# Module_control.net
KiCad netlist of a schematic drawn in EAGLE
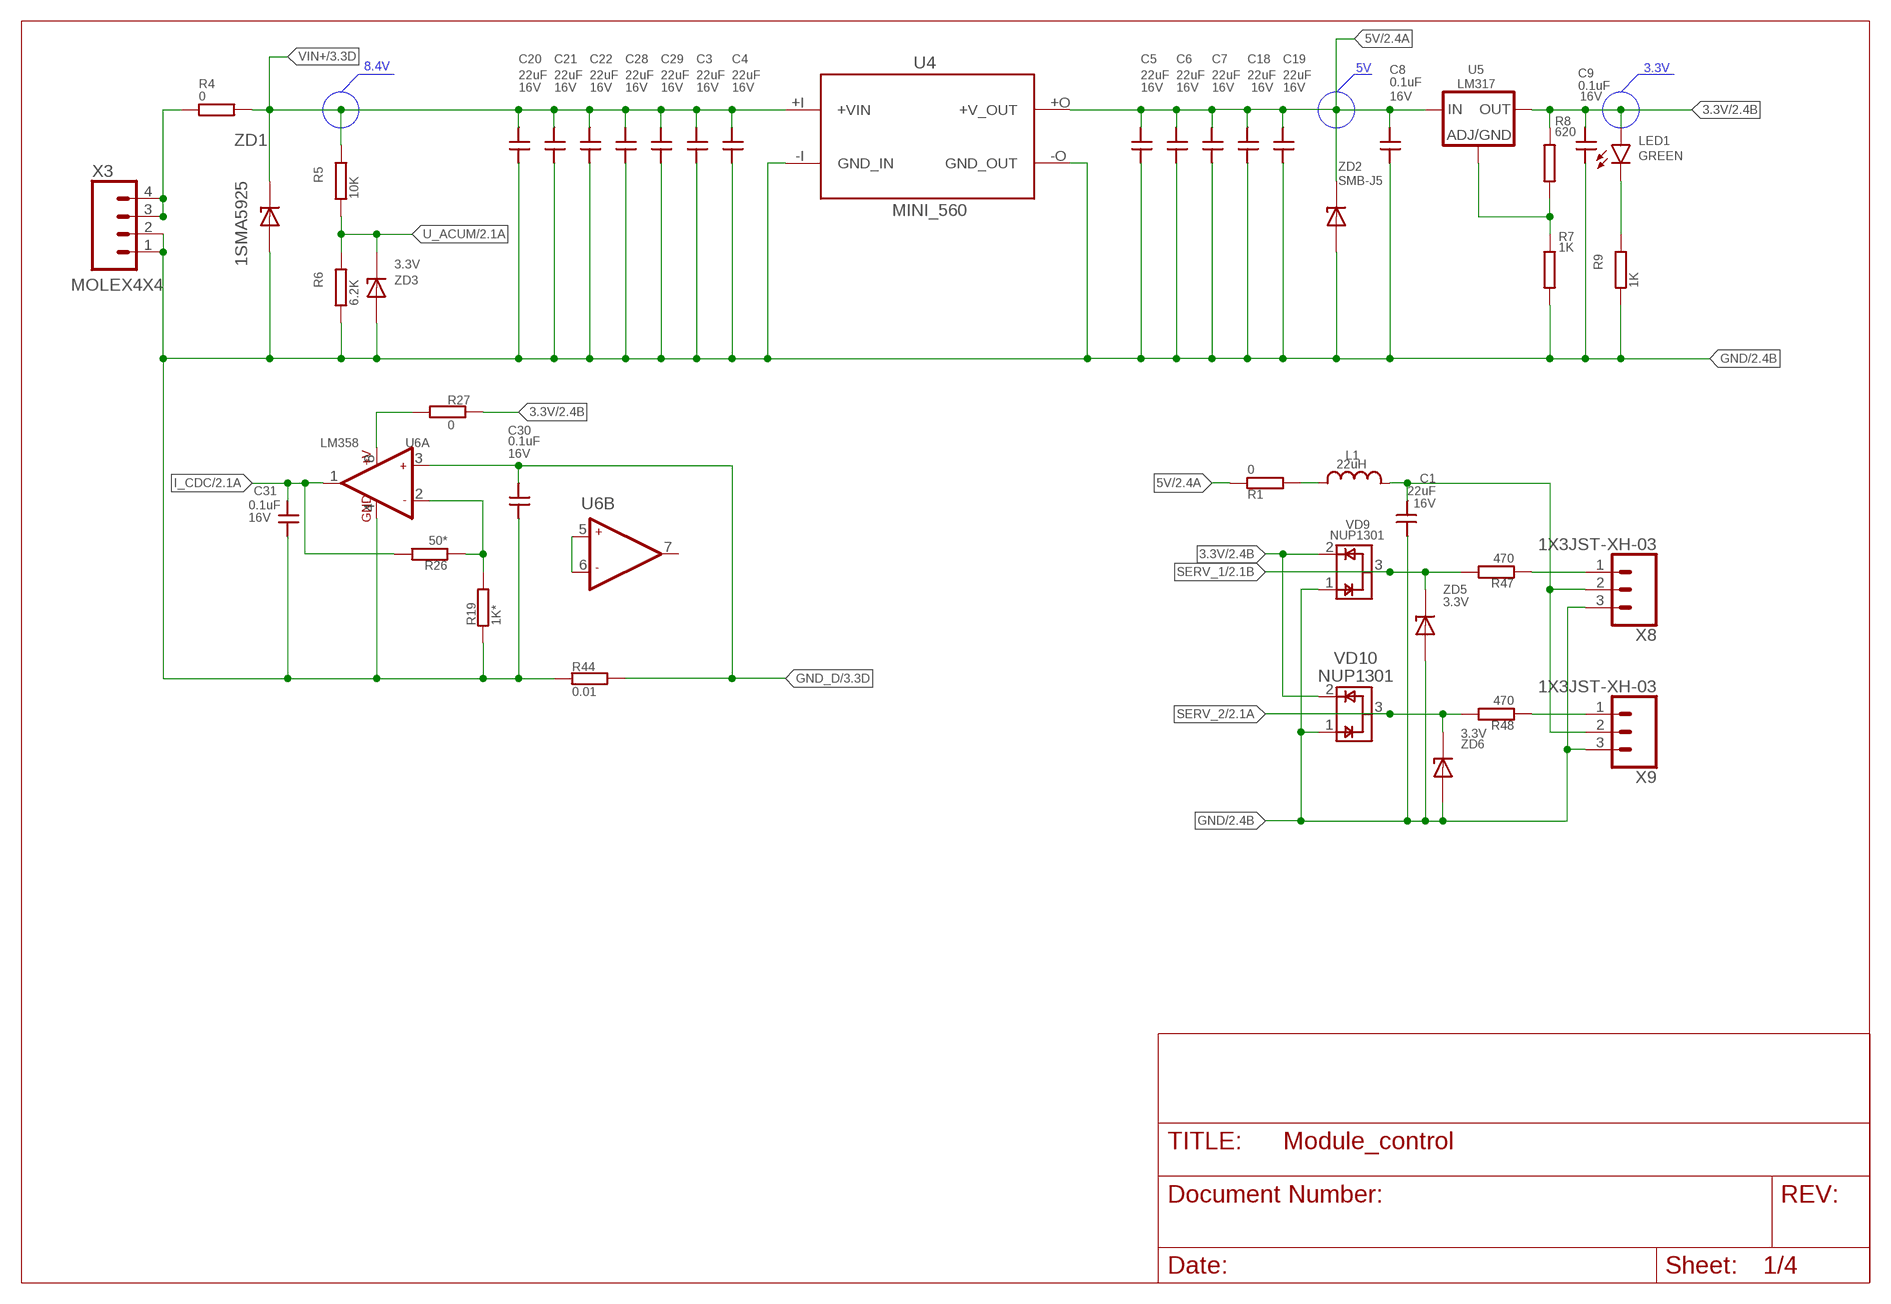
[diagram p0: schematic, sheet 1]
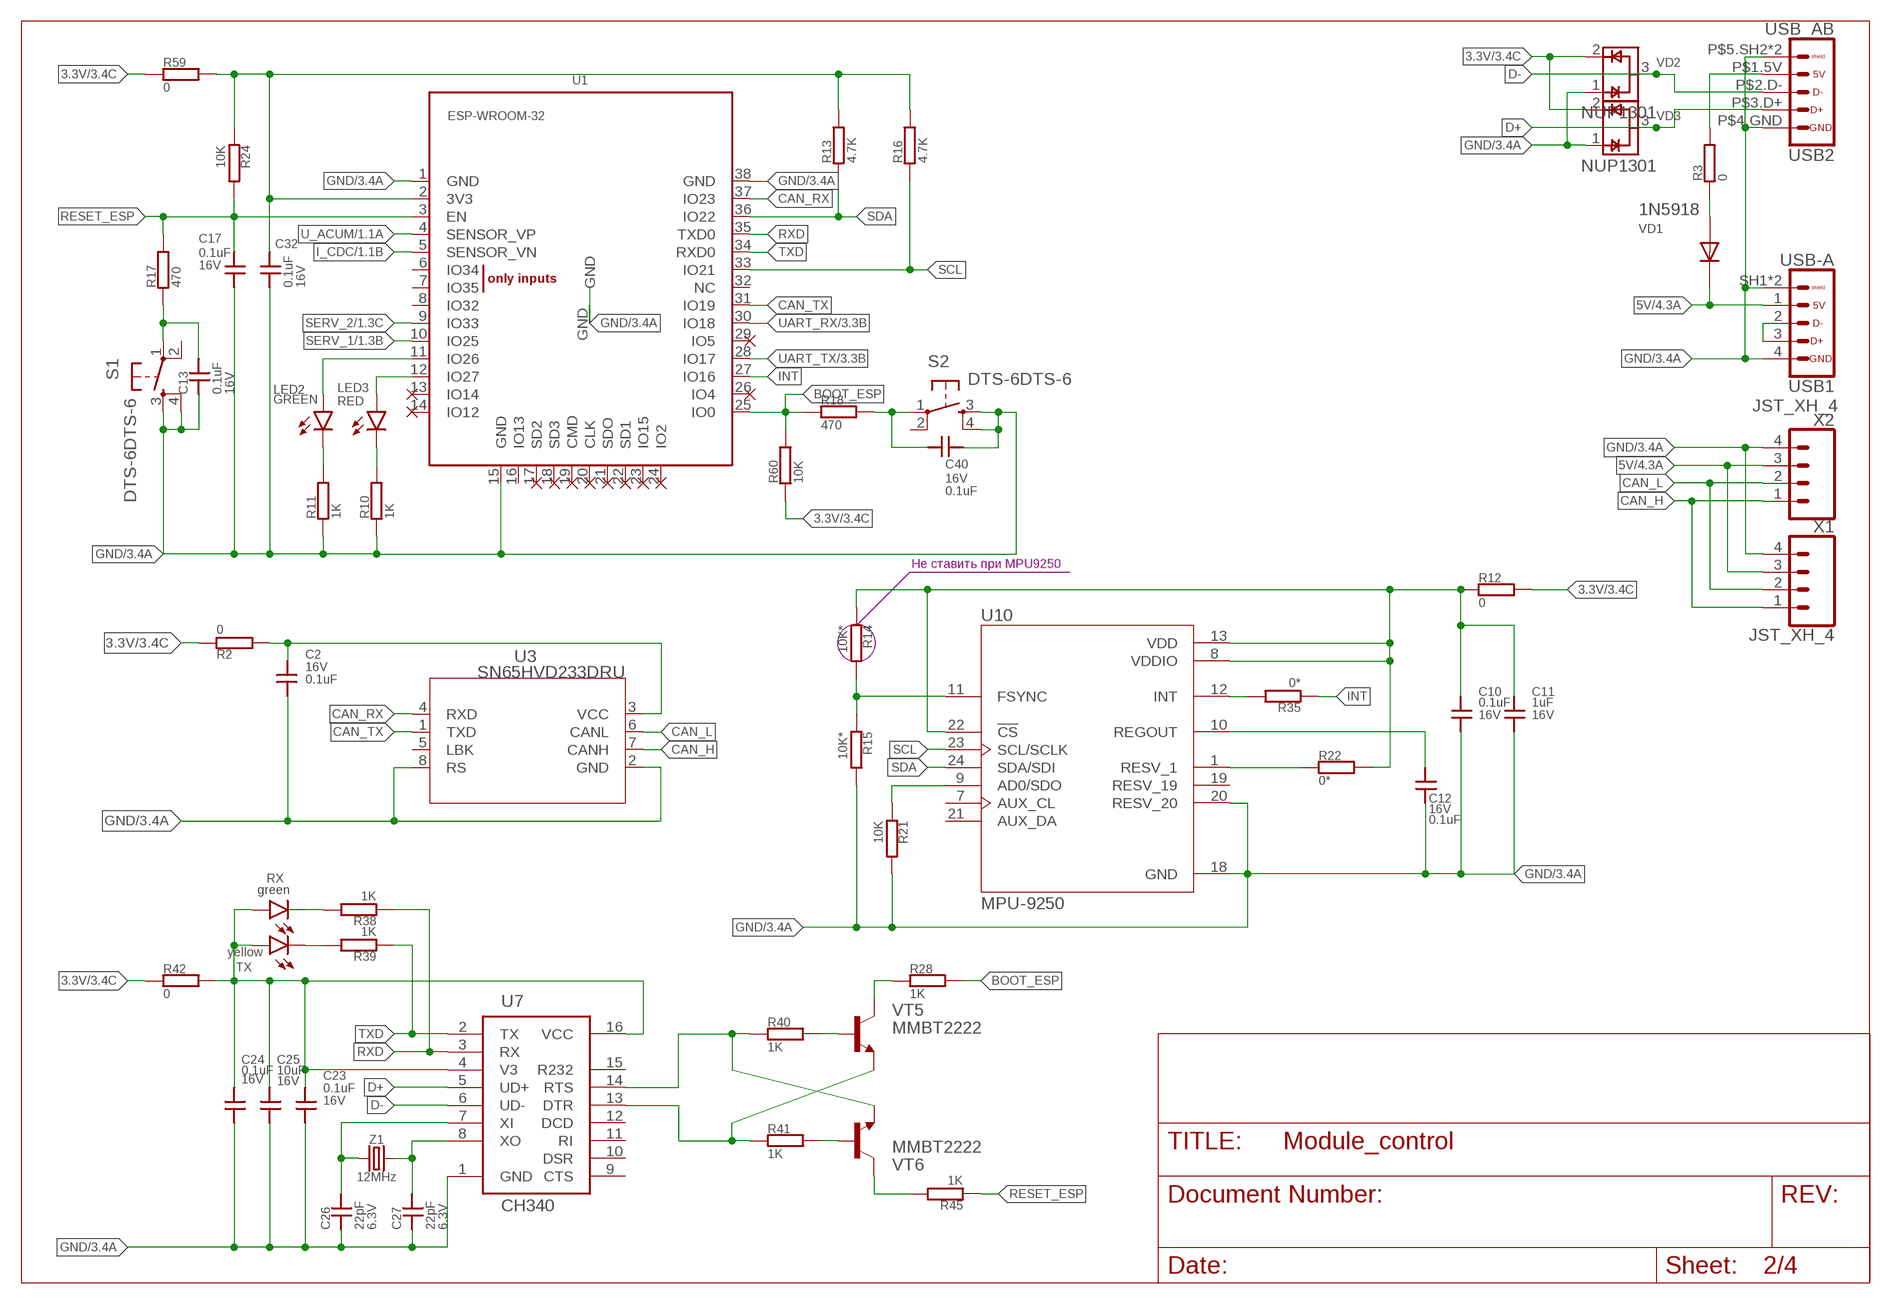
[diagram p1: schematic, sheet 2]
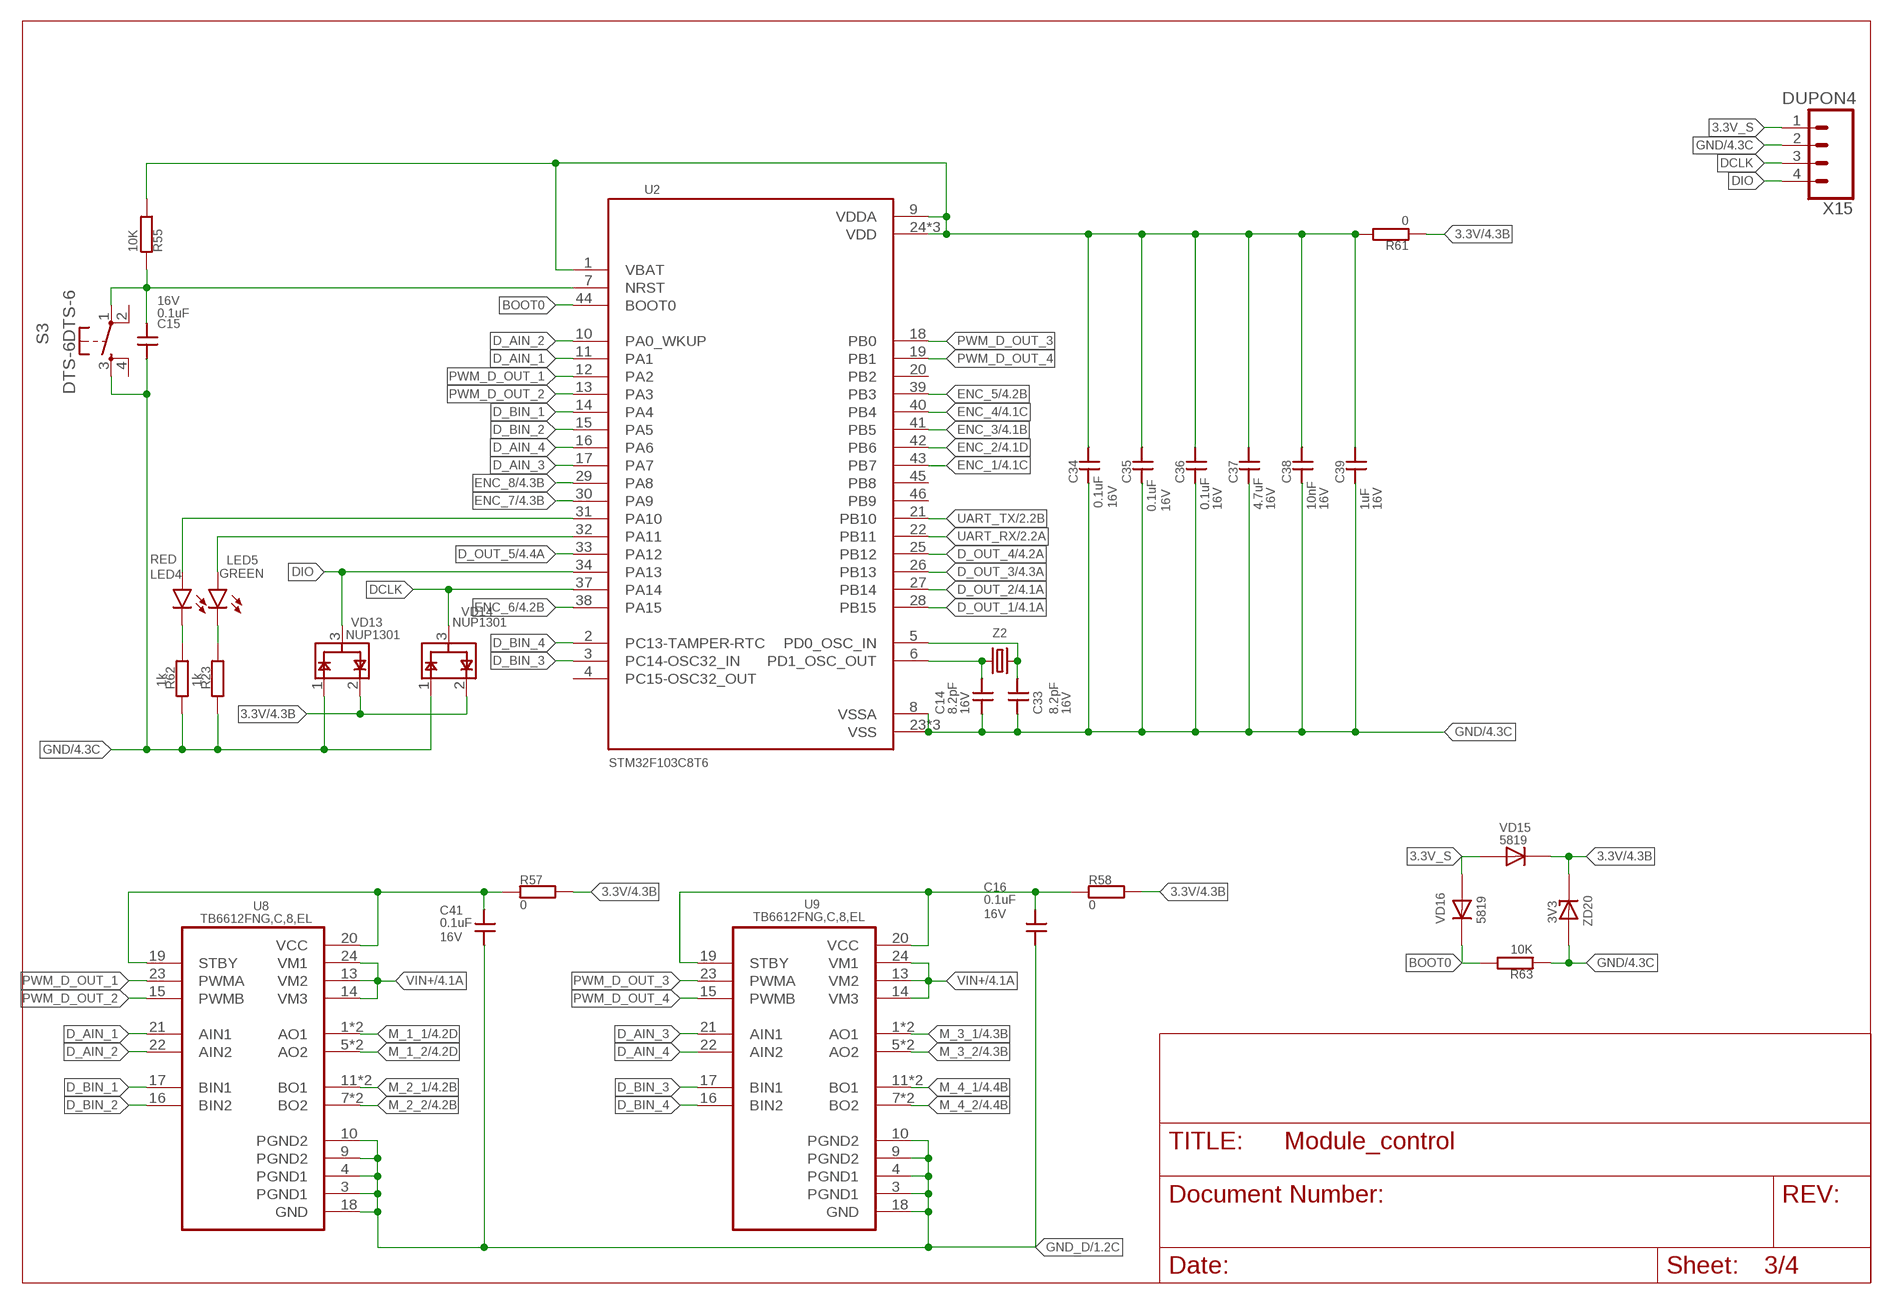
[diagram p2: schematic, sheet 3]
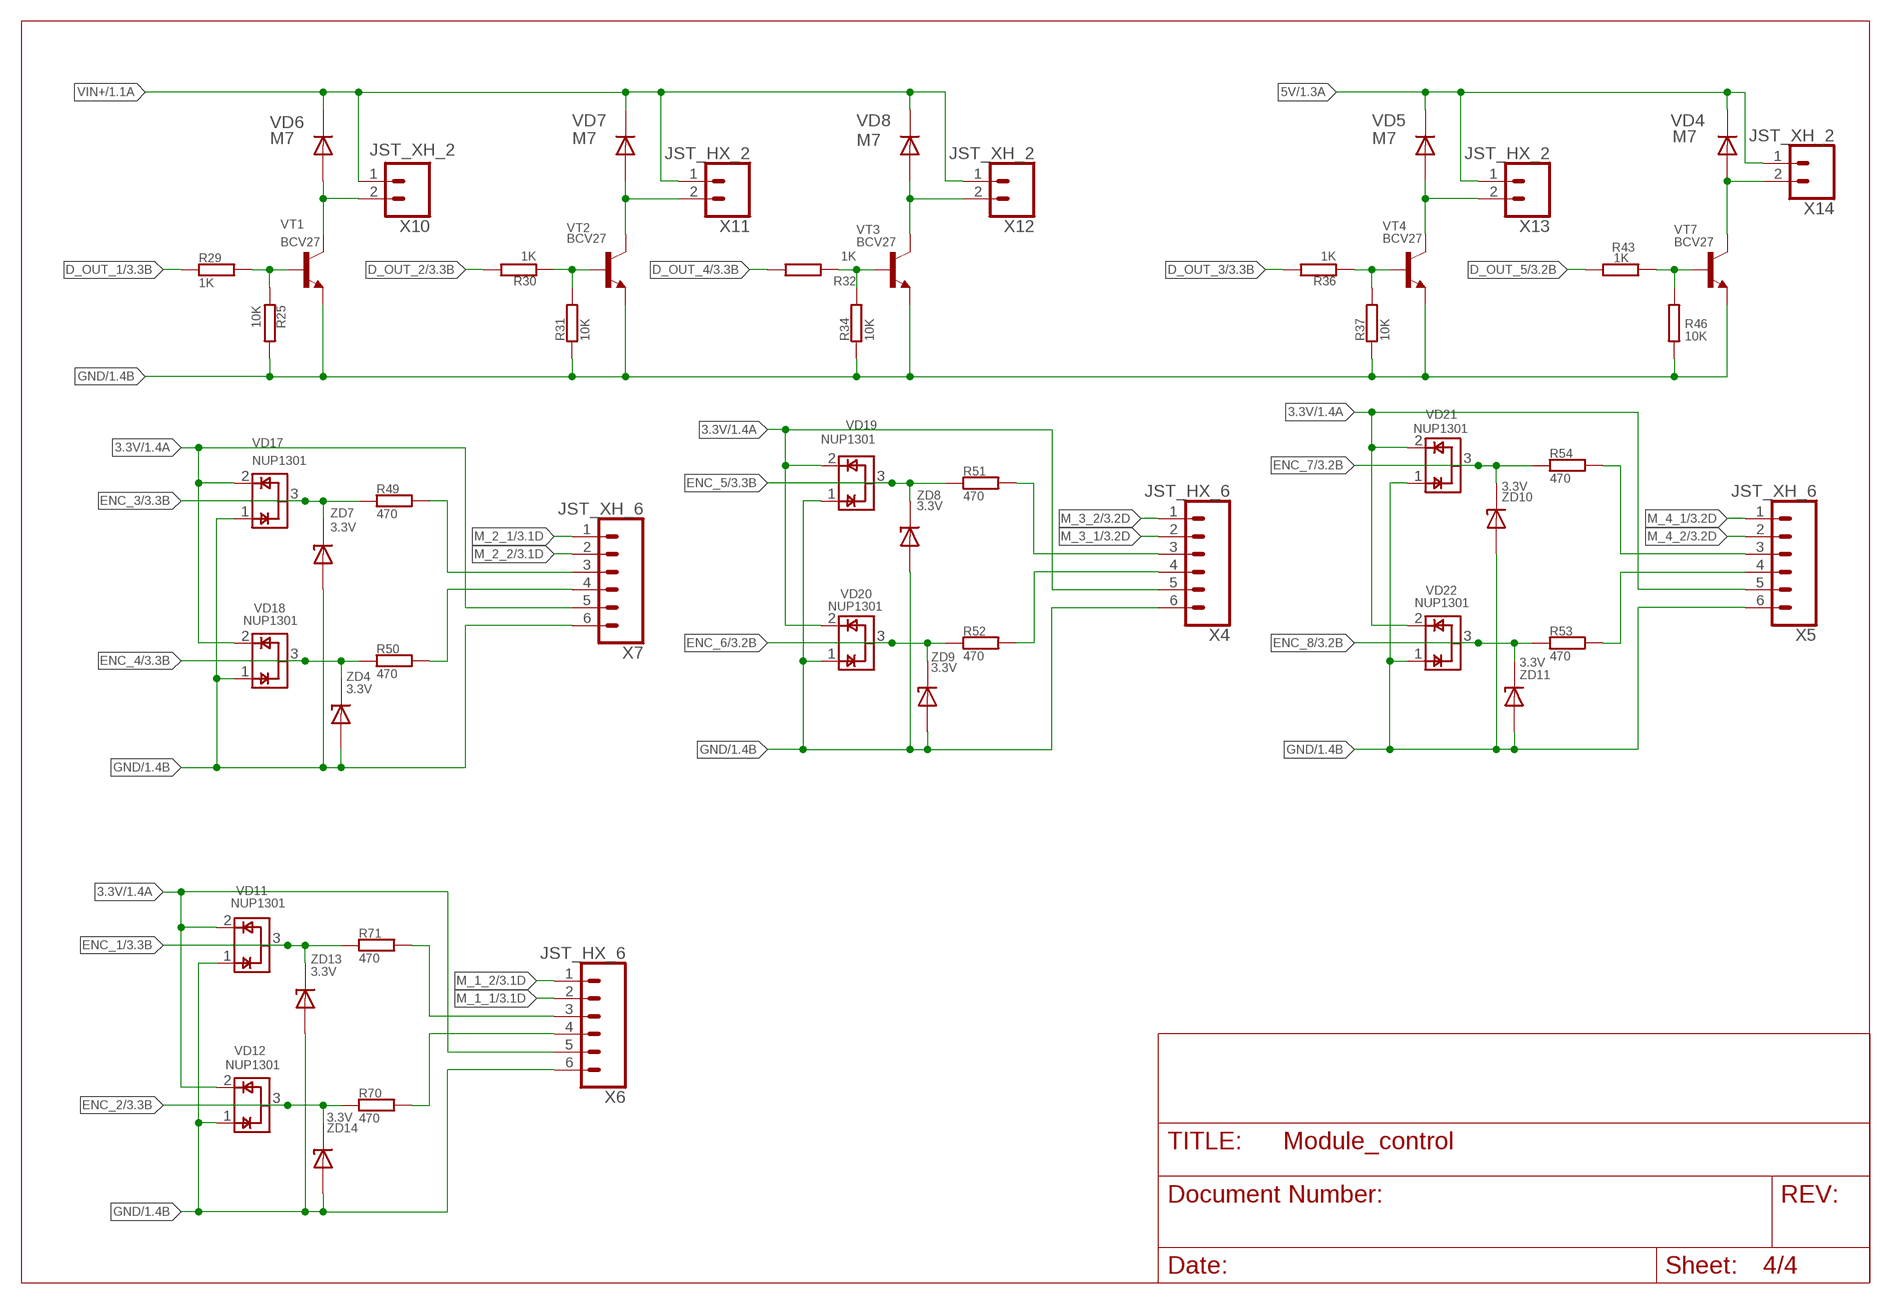
[diagram p3: schematic, sheet 4]

(export (version "E")
  (design (tool "Eeschema 10.0.6"))
  (components
    (comp (ref "C2")
      (value "0.1uF")
      (footprint "eagle-import:0603")
      (fields (field (name "VOLTAGE") "16V"))
      (libsource (lib "eagle-import") (part "C0603"))
    )
    (comp (ref "C10")
      (value "0.1uF")
      (footprint "eagle-import:0603")
      (fields (field (name "VOLTAGE") "16V"))
      (libsource (lib "eagle-import") (part "C0603"))
    )
    (comp (ref "C11")
      (value "1uF")
      (footprint "eagle-import:0603")
      (fields (field (name "VOLTAGE") "16V"))
      (libsource (lib "eagle-import") (part "C0603"))
    )
    (comp (ref "C12")
      (value "0.1uF")
      (footprint "eagle-import:0603")
      (fields (field (name "VOLTAGE") "16V"))
      (libsource (lib "eagle-import") (part "C0603"))
    )
    (comp (ref "C13")
      (value "0.1uF")
      (footprint "eagle-import:0603")
      (fields (field (name "VOLTAGE") "16V"))
      (libsource (lib "eagle-import") (part "C0603"))
    )
    (comp (ref "C17")
      (value "0.1uF")
      (footprint "eagle-import:0603")
      (fields (field (name "VOLTAGE") "16V"))
      (libsource (lib "eagle-import") (part "C0603"))
    )
    (comp (ref "C23")
      (value "0.1uF")
      (footprint "eagle-import:0603")
      (fields (field (name "VOLTAGE") "16V"))
      (libsource (lib "eagle-import") (part "C0603"))
    )
    (comp (ref "C24")
      (value "0.1uF")
      (footprint "eagle-import:0603")
      (fields (field (name "VOLTAGE") "16V"))
      (libsource (lib "eagle-import") (part "C0603"))
    )
    (comp (ref "C25")
      (value "10uF")
      (footprint "eagle-import:0603")
      (fields (field (name "VOLTAGE") "16V"))
      (libsource (lib "eagle-import") (part "C0603"))
    )
    (comp (ref "C26")
      (value "22pF")
      (footprint "eagle-import:0603")
      (fields (field (name "VOLTAGE") "6.3V"))
      (libsource (lib "eagle-import") (part "C0603"))
    )
    (comp (ref "C27")
      (value "22pF")
      (footprint "eagle-import:0603")
      (fields (field (name "VOLTAGE") "6.3V"))
      (libsource (lib "eagle-import") (part "C0603"))
    )
    (comp (ref "C32")
      (value "0.1uF")
      (footprint "eagle-import:0603")
      (fields (field (name "VOLTAGE") "16V"))
      (libsource (lib "eagle-import") (part "C0603"))
    )
    (comp (ref "C40")
      (value "0.1uF")
      (footprint "eagle-import:0603")
      (fields (field (name "VOLTAGE") "16V"))
      (libsource (lib "eagle-import") (part "C0603"))
    )
    (comp (ref "LED2")
      (value "GREEN")
      (footprint "eagle-import:1608")
      (libsource (lib "eagle-import") (part "LED1608"))
    )
    (comp (ref "LED3")
      (value "RED")
      (footprint "eagle-import:1608")
      (libsource (lib "eagle-import") (part "LED1608"))
    )
    (comp (ref "R2")
      (value "0")
      (footprint "eagle-import:0603")
      (libsource (lib "eagle-import") (part "R0603"))
    )
    (comp (ref "R3")
      (value "0")
      (footprint "eagle-import:0603")
      (libsource (lib "eagle-import") (part "R0603"))
    )
    (comp (ref "R10")
      (value "1K")
      (footprint "eagle-import:0603")
      (libsource (lib "eagle-import") (part "R0603"))
    )
    (comp (ref "R11")
      (value "1K")
      (footprint "eagle-import:0603")
      (libsource (lib "eagle-import") (part "R0603"))
    )
    (comp (ref "R12")
      (value "0")
      (footprint "eagle-import:0603")
      (libsource (lib "eagle-import") (part "R0603"))
    )
    (comp (ref "R13")
      (value "4.7K")
      (footprint "eagle-import:0603")
      (libsource (lib "eagle-import") (part "R0603"))
    )
    (comp (ref "R14")
      (value "10K*")
      (footprint "eagle-import:0603")
      (libsource (lib "eagle-import") (part "R0603"))
    )
    (comp (ref "R15")
      (value "10K*")
      (footprint "eagle-import:0603")
      (libsource (lib "eagle-import") (part "R0603"))
    )
    (comp (ref "R16")
      (value "4.7K")
      (footprint "eagle-import:0603")
      (libsource (lib "eagle-import") (part "R0603"))
    )
    (comp (ref "R17")
      (value "470")
      (footprint "eagle-import:0603")
      (libsource (lib "eagle-import") (part "R0603"))
    )
    (comp (ref "R18")
      (value "470")
      (footprint "eagle-import:0603")
      (libsource (lib "eagle-import") (part "R0603"))
    )
    (comp (ref "R21")
      (value "10K")
      (footprint "eagle-import:0603")
      (libsource (lib "eagle-import") (part "R0603"))
    )
    (comp (ref "R22")
      (value "0*")
      (footprint "eagle-import:0603")
      (libsource (lib "eagle-import") (part "R0603"))
    )
    (comp (ref "R24")
      (value "10K")
      (footprint "eagle-import:0603")
      (libsource (lib "eagle-import") (part "R0603"))
    )
    (comp (ref "R28")
      (value "1K")
      (footprint "eagle-import:0603")
      (libsource (lib "eagle-import") (part "R0603"))
    )
    (comp (ref "R35")
      (value "0*")
      (footprint "eagle-import:0603")
      (libsource (lib "eagle-import") (part "R0603"))
    )
    (comp (ref "R38")
      (value "1K")
      (footprint "eagle-import:0603")
      (libsource (lib "eagle-import") (part "R0603"))
    )
    (comp (ref "R39")
      (value "1K")
      (footprint "eagle-import:0603")
      (libsource (lib "eagle-import") (part "R0603"))
    )
    (comp (ref "R40")
      (value "1K")
      (footprint "eagle-import:0603")
      (libsource (lib "eagle-import") (part "R0603"))
    )
    (comp (ref "R41")
      (value "1K")
      (footprint "eagle-import:0603")
      (libsource (lib "eagle-import") (part "R0603"))
    )
    (comp (ref "R42")
      (value "0")
      (footprint "eagle-import:0603")
      (libsource (lib "eagle-import") (part "R0603"))
    )
    (comp (ref "R45")
      (value "1K")
      (footprint "eagle-import:0603")
      (libsource (lib "eagle-import") (part "R0603"))
    )
    (comp (ref "R59")
      (value "0")
      (footprint "eagle-import:0603")
      (libsource (lib "eagle-import") (part "R0603"))
    )
    (comp (ref "R60")
      (value "10K")
      (footprint "eagle-import:0603")
      (libsource (lib "eagle-import") (part "R0603"))
    )
    (comp (ref "RX")
      (value "green")
      (footprint "eagle-import:2013")
      (libsource (lib "eagle-import") (part "LED2013"))
    )
    (comp (ref "S1")
      (value "DTS-6DTS-6")
      (footprint "eagle-import:DTS-6")
      (libsource (lib "eagle-import") (part "DTS-6DTS-6"))
    )
    (comp (ref "S2")
      (value "DTS-6DTS-6")
      (footprint "eagle-import:DTS-6")
      (libsource (lib "eagle-import") (part "DTS-6DTS-6"))
    )
    (comp (ref "TX")
      (value "yellow")
      (footprint "eagle-import:2013")
      (libsource (lib "eagle-import") (part "LED2013"))
    )
    (comp (ref "U1")
      (value "ESP-WROOM-32")
      (footprint "eagle-import:ESP-WROOM-32")
      (libsource (lib "eagle-import") (part "ESP-WROOM-32"))
    )
    (comp (ref "U3")
      (value "SN65HVD233DRU")
      (footprint "eagle-import:SOIC-8")
      (libsource (lib "eagle-import") (part "SN65HVD233DRU"))
    )
    (comp (ref "U7")
      (value "CH340")
      (footprint "eagle-import:SOIC-16")
      (libsource (lib "eagle-import") (part "CH340"))
    )
    (comp (ref "U10")
      (value "MPU-9250")
      (footprint "eagle-import:QFN40P300X300X105-24N")
      (fields (field (name "MF") "TDK InvenSense"))
      (libsource (lib "eagle-import") (part "MPU-9250"))
    )
    (comp (ref "USB1")
      (value "USB-A")
      (footprint "eagle-import:A-VERTICAL")
      (libsource (lib "eagle-import") (part "USB-A"))
    )
    (comp (ref "USB2")
      (value "USB_AB")
      (footprint "eagle-import:B-VERTICAL")
      (libsource (lib "eagle-import") (part "USB-B"))
    )
    (comp (ref "VD1")
      (value "1N5918")
      (footprint "eagle-import:SOD123")
      (libsource (lib "eagle-import") (part "DIODESOD-123"))
    )
    (comp (ref "VD2")
      (value "NUP1301")
      (footprint "eagle-import:SOT23")
      (libsource (lib "eagle-import") (part "ESD_PROTECTIONSOT123"))
    )
    (comp (ref "VD3")
      (value "NUP1301")
      (footprint "eagle-import:SOT23")
      (libsource (lib "eagle-import") (part "ESD_PROTECTIONSOT123"))
    )
    (comp (ref "VT5")
      (value "MMBT2222")
      (footprint "eagle-import:SOT-23")
      (libsource (lib "eagle-import") (part "NPNSOT-23"))
    )
    (comp (ref "VT6")
      (value "MMBT2222")
      (footprint "eagle-import:SOT-23")
      (libsource (lib "eagle-import") (part "NPNSOT-23"))
    )
    (comp (ref "X1")
      (value "JST_XH_4")
      (footprint "eagle-import:JST-XH-04")
      (libsource (lib "eagle-import") (part "1X4JST-XH-04"))
    )
    (comp (ref "X2")
      (value "JST_XH_4")
      (footprint "eagle-import:JST-XH-04")
      (libsource (lib "eagle-import") (part "1X4JST-XH-04"))
    )
    (comp (ref "Z1")
      (value "12MHz")
      (footprint "eagle-import:CRYSTAL-SMD-3.2X2.5MM")
      (libsource (lib "eagle-import") (part "CRYSTAL4FOOT"))
    )
    (comp (ref "R25")
      (value "10K")
      (footprint "eagle-import:0603")
      (libsource (lib "eagle-import") (part "R0603"))
    )
    (comp (ref "R29")
      (value "1K")
      (footprint "eagle-import:0603")
      (libsource (lib "eagle-import") (part "R0603"))
    )
    (comp (ref "R30")
      (value "1K")
      (footprint "eagle-import:0603")
      (libsource (lib "eagle-import") (part "R0603"))
    )
    (comp (ref "R31")
      (value "10K")
      (footprint "eagle-import:0603")
      (libsource (lib "eagle-import") (part "R0603"))
    )
    (comp (ref "R32")
      (value "1K")
      (footprint "eagle-import:0603")
      (libsource (lib "eagle-import") (part "R0603"))
    )
    (comp (ref "R34")
      (value "10K")
      (footprint "eagle-import:0603")
      (libsource (lib "eagle-import") (part "R0603"))
    )
    (comp (ref "R36")
      (value "1K")
      (footprint "eagle-import:0603")
      (libsource (lib "eagle-import") (part "R0603"))
    )
    (comp (ref "R37")
      (value "10K")
      (footprint "eagle-import:0603")
      (libsource (lib "eagle-import") (part "R0603"))
    )
    (comp (ref "R43")
      (value "1K")
      (footprint "eagle-import:0603")
      (libsource (lib "eagle-import") (part "R0603"))
    )
    (comp (ref "R46")
      (value "10K")
      (footprint "eagle-import:0603")
      (libsource (lib "eagle-import") (part "R0603"))
    )
    (comp (ref "R49")
      (value "470")
      (footprint "eagle-import:0603")
      (libsource (lib "eagle-import") (part "R0603"))
    )
    (comp (ref "R50")
      (value "470")
      (footprint "eagle-import:0603")
      (libsource (lib "eagle-import") (part "R0603"))
    )
    (comp (ref "R51")
      (value "470")
      (footprint "eagle-import:0603")
      (libsource (lib "eagle-import") (part "R0603"))
    )
    (comp (ref "R52")
      (value "470")
      (footprint "eagle-import:0603")
      (libsource (lib "eagle-import") (part "R0603"))
    )
    (comp (ref "R53")
      (value "470")
      (footprint "eagle-import:0603")
      (libsource (lib "eagle-import") (part "R0603"))
    )
    (comp (ref "R54")
      (value "470")
      (footprint "eagle-import:0603")
      (libsource (lib "eagle-import") (part "R0603"))
    )
    (comp (ref "R70")
      (value "470")
      (footprint "eagle-import:0603")
      (libsource (lib "eagle-import") (part "R0603"))
    )
    (comp (ref "R71")
      (value "470")
      (footprint "eagle-import:0603")
      (libsource (lib "eagle-import") (part "R0603"))
    )
    (comp (ref "VD4")
      (value "M7")
      (footprint "eagle-import:SMA")
      (libsource (lib "eagle-import") (part "DIODESMA"))
    )
    (comp (ref "VD5")
      (value "M7")
      (footprint "eagle-import:SMA")
      (libsource (lib "eagle-import") (part "DIODESMA"))
    )
    (comp (ref "VD6")
      (value "M7")
      (footprint "eagle-import:SMA")
      (libsource (lib "eagle-import") (part "DIODESMA"))
    )
    (comp (ref "VD7")
      (value "M7")
      (footprint "eagle-import:SMA")
      (libsource (lib "eagle-import") (part "DIODESMA"))
    )
    (comp (ref "VD8")
      (value "M7")
      (footprint "eagle-import:SMA")
      (libsource (lib "eagle-import") (part "DIODESMA"))
    )
    (comp (ref "VD11")
      (value "NUP1301")
      (footprint "eagle-import:SOT23")
      (libsource (lib "eagle-import") (part "ESD_PROTECTIONSOT123"))
    )
    (comp (ref "VD12")
      (value "NUP1301")
      (footprint "eagle-import:SOT23")
      (libsource (lib "eagle-import") (part "ESD_PROTECTIONSOT123"))
    )
    (comp (ref "VD17")
      (value "NUP1301")
      (footprint "eagle-import:SOT23")
      (libsource (lib "eagle-import") (part "ESD_PROTECTIONSOT123"))
    )
    (comp (ref "VD18")
      (value "NUP1301")
      (footprint "eagle-import:SOT23")
      (libsource (lib "eagle-import") (part "ESD_PROTECTIONSOT123"))
    )
    (comp (ref "VD19")
      (value "NUP1301")
      (footprint "eagle-import:SOT23")
      (libsource (lib "eagle-import") (part "ESD_PROTECTIONSOT123"))
    )
    (comp (ref "VD20")
      (value "NUP1301")
      (footprint "eagle-import:SOT23")
      (libsource (lib "eagle-import") (part "ESD_PROTECTIONSOT123"))
    )
    (comp (ref "VD21")
      (value "NUP1301")
      (footprint "eagle-import:SOT23")
      (libsource (lib "eagle-import") (part "ESD_PROTECTIONSOT123"))
    )
    (comp (ref "VD22")
      (value "NUP1301")
      (footprint "eagle-import:SOT23")
      (libsource (lib "eagle-import") (part "ESD_PROTECTIONSOT123"))
    )
    (comp (ref "VT1")
      (value "BCV27")
      (footprint "eagle-import:SOT-23")
      (libsource (lib "eagle-import") (part "NPNSOT-23"))
    )
    (comp (ref "VT2")
      (value "BCV27")
      (footprint "eagle-import:SOT-23")
      (libsource (lib "eagle-import") (part "NPNSOT-23"))
    )
    (comp (ref "VT3")
      (value "BCV27")
      (footprint "eagle-import:SOT-23")
      (libsource (lib "eagle-import") (part "NPNSOT-23"))
    )
    (comp (ref "VT4")
      (value "BCV27")
      (footprint "eagle-import:SOT-23")
      (libsource (lib "eagle-import") (part "NPNSOT-23"))
    )
    (comp (ref "VT7")
      (value "BCV27")
      (footprint "eagle-import:SOT-23")
      (libsource (lib "eagle-import") (part "NPNSOT-23"))
    )
    (comp (ref "X4")
      (value "JST_HX_6")
      (footprint "eagle-import:JST-XH-06")
      (libsource (lib "eagle-import") (part "1X6JST-XH-06"))
    )
    (comp (ref "X5")
      (value "JST_XH_6")
      (footprint "eagle-import:JST-XH-06")
      (libsource (lib "eagle-import") (part "1X6JST-XH-06"))
    )
    (comp (ref "X6")
      (value "JST_HX_6")
      (footprint "eagle-import:JST-XH-06")
      (libsource (lib "eagle-import") (part "1X6JST-XH-06"))
    )
    (comp (ref "X7")
      (value "JST_XH_6")
      (footprint "eagle-import:JST-XH-06")
      (libsource (lib "eagle-import") (part "1X6JST-XH-06"))
    )
    (comp (ref "X10")
      (value "JST_XH_2")
      (footprint "eagle-import:JST-XH-02")
      (libsource (lib "eagle-import") (part "1X2JST-XH-02"))
    )
    (comp (ref "X11")
      (value "JST_HX_2")
      (footprint "eagle-import:JST-XH-02")
      (libsource (lib "eagle-import") (part "1X2JST-XH-02"))
    )
    (comp (ref "X12")
      (value "JST_XH_2")
      (footprint "eagle-import:JST-XH-02")
      (libsource (lib "eagle-import") (part "1X2JST-XH-02"))
    )
    (comp (ref "X13")
      (value "JST_HX_2")
      (footprint "eagle-import:JST-XH-02")
      (libsource (lib "eagle-import") (part "1X2JST-XH-02"))
    )
    (comp (ref "X14")
      (value "JST_XH_2")
      (footprint "eagle-import:JST-XH-02")
      (libsource (lib "eagle-import") (part "1X2JST-XH-02"))
    )
    (comp (ref "ZD4")
      (value "3.3V")
      (footprint "eagle-import:MINIMELF")
      (libsource (lib "eagle-import") (part "ZENER-DIODESMINIMELF"))
    )
    (comp (ref "ZD7")
      (value "3.3V")
      (footprint "eagle-import:MINIMELF")
      (libsource (lib "eagle-import") (part "ZENER-DIODESMINIMELF"))
    )
    (comp (ref "ZD8")
      (value "3.3V")
      (footprint "eagle-import:MINIMELF")
      (libsource (lib "eagle-import") (part "ZENER-DIODESMINIMELF"))
    )
    (comp (ref "ZD9")
      (value "3.3V")
      (footprint "eagle-import:MINIMELF")
      (libsource (lib "eagle-import") (part "ZENER-DIODESMINIMELF"))
    )
    (comp (ref "ZD10")
      (value "3.3V")
      (footprint "eagle-import:MINIMELF")
      (libsource (lib "eagle-import") (part "ZENER-DIODESMINIMELF"))
    )
    (comp (ref "ZD11")
      (value "3.3V")
      (footprint "eagle-import:MINIMELF")
      (libsource (lib "eagle-import") (part "ZENER-DIODESMINIMELF"))
    )
    (comp (ref "ZD13")
      (value "3.3V")
      (footprint "eagle-import:MINIMELF")
      (libsource (lib "eagle-import") (part "ZENER-DIODESMINIMELF"))
    )
    (comp (ref "ZD14")
      (value "3.3V")
      (footprint "eagle-import:MINIMELF")
      (libsource (lib "eagle-import") (part "ZENER-DIODESMINIMELF"))
    )
    (comp (ref "C1")
      (value "22uF")
      (footprint "eagle-import:1206")
      (fields (field (name "VOLTAGE") "16V"))
      (libsource (lib "eagle-import") (part "C1206"))
    )
    (comp (ref "C3")
      (value "22uF")
      (footprint "eagle-import:1206")
      (fields (field (name "VOLTAGE") "16V"))
      (libsource (lib "eagle-import") (part "C1206"))
    )
    (comp (ref "C4")
      (value "22uF")
      (footprint "eagle-import:1206")
      (fields (field (name "VOLTAGE") "16V"))
      (libsource (lib "eagle-import") (part "C1206"))
    )
    (comp (ref "C5")
      (value "22uF")
      (footprint "eagle-import:1206")
      (fields (field (name "VOLTAGE") "16V"))
      (libsource (lib "eagle-import") (part "C1206"))
    )
    (comp (ref "C6")
      (value "22uF")
      (footprint "eagle-import:1206")
      (fields (field (name "VOLTAGE") "16V"))
      (libsource (lib "eagle-import") (part "C1206"))
    )
    (comp (ref "C7")
      (value "22uF")
      (footprint "eagle-import:1206")
      (fields (field (name "VOLTAGE") "16V"))
      (libsource (lib "eagle-import") (part "C1206"))
    )
    (comp (ref "C8")
      (value "0.1uF")
      (footprint "eagle-import:0603")
      (fields (field (name "VOLTAGE") "16V"))
      (libsource (lib "eagle-import") (part "C0603"))
    )
    (comp (ref "C9")
      (value "0.1uF")
      (footprint "eagle-import:0603")
      (fields (field (name "VOLTAGE") "16V"))
      (libsource (lib "eagle-import") (part "C0603"))
    )
    (comp (ref "C18")
      (value "22uF")
      (footprint "eagle-import:1206")
      (fields (field (name "VOLTAGE") "16V"))
      (libsource (lib "eagle-import") (part "C1206"))
    )
    (comp (ref "C19")
      (value "22uF")
      (footprint "eagle-import:1206")
      (fields (field (name "VOLTAGE") "16V"))
      (libsource (lib "eagle-import") (part "C1206"))
    )
    (comp (ref "C20")
      (value "22uF")
      (footprint "eagle-import:1206")
      (fields (field (name "VOLTAGE") "16V"))
      (libsource (lib "eagle-import") (part "C1206"))
    )
    (comp (ref "C21")
      (value "22uF")
      (footprint "eagle-import:1206")
      (fields (field (name "VOLTAGE") "16V"))
      (libsource (lib "eagle-import") (part "C1206"))
    )
    (comp (ref "C22")
      (value "22uF")
      (footprint "eagle-import:1206")
      (fields (field (name "VOLTAGE") "16V"))
      (libsource (lib "eagle-import") (part "C1206"))
    )
    (comp (ref "C28")
      (value "22uF")
      (footprint "eagle-import:1206")
      (fields (field (name "VOLTAGE") "16V"))
      (libsource (lib "eagle-import") (part "C1206"))
    )
    (comp (ref "C29")
      (value "22uF")
      (footprint "eagle-import:1206")
      (fields (field (name "VOLTAGE") "16V"))
      (libsource (lib "eagle-import") (part "C1206"))
    )
    (comp (ref "C30")
      (value "0.1uF")
      (footprint "eagle-import:0603")
      (fields (field (name "VOLTAGE") "16V"))
      (libsource (lib "eagle-import") (part "C0603"))
    )
    (comp (ref "C31")
      (value "0.1uF")
      (footprint "eagle-import:0603")
      (fields (field (name "VOLTAGE") "16V"))
      (libsource (lib "eagle-import") (part "C0603"))
    )
    (comp (ref "L1")
      (value "22uH")
      (footprint "eagle-import:0420CDMC")
      (libsource (lib "eagle-import") (part "INDUCTOR0420CDMC"))
    )
    (comp (ref "LED1")
      (value "GREEN")
      (footprint "eagle-import:1608")
      (libsource (lib "eagle-import") (part "LED1608"))
    )
    (comp (ref "R1")
      (value "0")
      (footprint "eagle-import:0603")
      (libsource (lib "eagle-import") (part "R0603"))
    )
    (comp (ref "R4")
      (value "0")
      (footprint "eagle-import:2512")
      (libsource (lib "eagle-import") (part "R2512"))
    )
    (comp (ref "R5")
      (value "10K")
      (footprint "eagle-import:0603")
      (libsource (lib "eagle-import") (part "R0603"))
    )
    (comp (ref "R6")
      (value "6.2K")
      (footprint "eagle-import:0603")
      (libsource (lib "eagle-import") (part "R0603"))
    )
    (comp (ref "R7")
      (value "1K")
      (footprint "eagle-import:0603")
      (libsource (lib "eagle-import") (part "R0603"))
    )
    (comp (ref "R8")
      (value "620")
      (footprint "eagle-import:0603")
      (libsource (lib "eagle-import") (part "R0603"))
    )
    (comp (ref "R9")
      (value "1K")
      (footprint "eagle-import:0603")
      (libsource (lib "eagle-import") (part "R0603"))
    )
    (comp (ref "R19")
      (value "1K*")
      (footprint "eagle-import:0603")
      (libsource (lib "eagle-import") (part "R0603"))
    )
    (comp (ref "R26")
      (value "50*")
      (footprint "eagle-import:0603")
      (libsource (lib "eagle-import") (part "R0603"))
    )
    (comp (ref "R27")
      (value "0")
      (footprint "eagle-import:0603")
      (libsource (lib "eagle-import") (part "R0603"))
    )
    (comp (ref "R44")
      (value "0.01")
      (footprint "eagle-import:1206")
      (libsource (lib "eagle-import") (part "R1206"))
    )
    (comp (ref "R47")
      (value "470")
      (footprint "eagle-import:0603")
      (libsource (lib "eagle-import") (part "R0603"))
    )
    (comp (ref "R48")
      (value "470")
      (footprint "eagle-import:0603")
      (libsource (lib "eagle-import") (part "R0603"))
    )
    (comp (ref "U4")
      (value "MINI_560")
      (footprint "eagle-import:MINI560_OTB")
      (libsource (lib "eagle-import") (part "MINI560"))
    )
    (comp (ref "U5")
      (value "LM317")
      (footprint "eagle-import:D-PAK")
      (libsource (lib "eagle-import") (part "LM317"))
    )
    (comp (ref "U6")
      (value "LM358")
      (footprint "eagle-import:SOIC-8")
      (libsource (lib "eagle-import") (part "OPAMPDUALU"))
    )
    (comp (ref "VD9")
      (value "NUP1301")
      (footprint "eagle-import:SOT23")
      (libsource (lib "eagle-import") (part "ESD_PROTECTIONSOT123"))
    )
    (comp (ref "VD10")
      (value "NUP1301")
      (footprint "eagle-import:SOT23")
      (libsource (lib "eagle-import") (part "ESD_PROTECTIONSOT123"))
    )
    (comp (ref "X3")
      (value "MOLEX4X4")
      (footprint "eagle-import:MOLEX-2X2U")
      (libsource (lib "eagle-import") (part "1X4MOLEX-2X2U"))
    )
    (comp (ref "X8")
      (value "1X3JST-XH-03")
      (footprint "eagle-import:JST-XH-03")
      (libsource (lib "eagle-import") (part "1X3JST-XH-03"))
    )
    (comp (ref "X9")
      (value "1X3JST-XH-03")
      (footprint "eagle-import:JST-XH-03")
      (libsource (lib "eagle-import") (part "1X3JST-XH-03"))
    )
    (comp (ref "ZD1")
      (value "1SMA5925")
      (footprint "eagle-import:SMB")
      (libsource (lib "eagle-import") (part "ZENER-DIODESSMB"))
    )
    (comp (ref "ZD2")
      (value "SMB-J5")
      (footprint "eagle-import:SMB")
      (libsource (lib "eagle-import") (part "ZENER-DIODESSMB"))
    )
    (comp (ref "ZD3")
      (value "3.3V")
      (footprint "eagle-import:MINIMELF")
      (libsource (lib "eagle-import") (part "ZENER-DIODESMINIMELF"))
    )
    (comp (ref "ZD5")
      (value "3.3V")
      (footprint "eagle-import:MINIMELF")
      (libsource (lib "eagle-import") (part "ZENER-DIODESMINIMELF"))
    )
    (comp (ref "ZD6")
      (value "3.3V")
      (footprint "eagle-import:MINIMELF")
      (libsource (lib "eagle-import") (part "ZENER-DIODESMINIMELF"))
    )
    (comp (ref "C14")
      (value "8.2pF")
      (footprint "eagle-import:0603")
      (fields (field (name "VOLTAGE") "16V"))
      (libsource (lib "eagle-import") (part "C0603"))
    )
    (comp (ref "C15")
      (value "0.1uF")
      (footprint "eagle-import:0603")
      (fields (field (name "VOLTAGE") "16V"))
      (libsource (lib "eagle-import") (part "C0603"))
    )
    (comp (ref "C16")
      (value "0.1uF")
      (footprint "eagle-import:0603")
      (fields (field (name "VOLTAGE") "16V"))
      (libsource (lib "eagle-import") (part "C0603"))
    )
    (comp (ref "C33")
      (value "8.2pF")
      (footprint "eagle-import:0603")
      (fields (field (name "VOLTAGE") "16V"))
      (libsource (lib "eagle-import") (part "C0603"))
    )
    (comp (ref "C34")
      (value "0.1uF")
      (footprint "eagle-import:0603")
      (fields (field (name "VOLTAGE") "16V"))
      (libsource (lib "eagle-import") (part "C0603"))
    )
    (comp (ref "C35")
      (value "0.1uF")
      (footprint "eagle-import:0603")
      (fields (field (name "VOLTAGE") "16V"))
      (libsource (lib "eagle-import") (part "C0603"))
    )
    (comp (ref "C36")
      (value "0.1uF")
      (footprint "eagle-import:0603")
      (fields (field (name "VOLTAGE") "16V"))
      (libsource (lib "eagle-import") (part "C0603"))
    )
    (comp (ref "C37")
      (value "4.7uF")
      (footprint "eagle-import:0603")
      (fields (field (name "VOLTAGE") "16V"))
      (libsource (lib "eagle-import") (part "C0603"))
    )
    (comp (ref "C38")
      (value "10nF")
      (footprint "eagle-import:0603")
      (fields (field (name "VOLTAGE") "16V"))
      (libsource (lib "eagle-import") (part "C0603"))
    )
    (comp (ref "C39")
      (value "1uF")
      (footprint "eagle-import:0603")
      (fields (field (name "VOLTAGE") "16V"))
      (libsource (lib "eagle-import") (part "C0603"))
    )
    (comp (ref "C41")
      (value "0.1uF")
      (footprint "eagle-import:0603")
      (fields (field (name "VOLTAGE") "16V"))
      (libsource (lib "eagle-import") (part "C0603"))
    )
    (comp (ref "LED4")
      (value "RED")
      (footprint "eagle-import:1608")
      (libsource (lib "eagle-import") (part "LED1608"))
    )
    (comp (ref "LED5")
      (value "GREEN")
      (footprint "eagle-import:1608")
      (libsource (lib "eagle-import") (part "LED1608"))
    )
    (comp (ref "R23")
      (value "1k")
      (footprint "eagle-import:0603")
      (libsource (lib "eagle-import") (part "R0603"))
    )
    (comp (ref "R55")
      (value "10K")
      (footprint "eagle-import:0603")
      (libsource (lib "eagle-import") (part "R0603"))
    )
    (comp (ref "R57")
      (value "0")
      (footprint "eagle-import:0603")
      (libsource (lib "eagle-import") (part "R0603"))
    )
    (comp (ref "R58")
      (value "0")
      (footprint "eagle-import:0603")
      (libsource (lib "eagle-import") (part "R0603"))
    )
    (comp (ref "R61")
      (value "0")
      (footprint "eagle-import:0603")
      (libsource (lib "eagle-import") (part "R0603"))
    )
    (comp (ref "R62")
      (value "1k")
      (footprint "eagle-import:0603")
      (libsource (lib "eagle-import") (part "R0603"))
    )
    (comp (ref "R63")
      (value "10K")
      (footprint "eagle-import:0603")
      (libsource (lib "eagle-import") (part "R0603"))
    )
    (comp (ref "S3")
      (value "DTS-6DTS-6")
      (footprint "eagle-import:DTS-6")
      (libsource (lib "eagle-import") (part "DTS-6DTS-6"))
    )
    (comp (ref "U2")
      (value "STM32F103C8T6")
      (footprint "eagle-import:QFP50P900X900X160-48N")
      (libsource (lib "eagle-import") (part "STM32F103C8T6"))
    )
    (comp (ref "U8")
      (value "TB6612FNG,C,8,EL")
      (footprint "eagle-import:SOP65")
      (libsource (lib "eagle-import") (part "TB6612FNG,C,8,EL"))
    )
    (comp (ref "U9")
      (value "TB6612FNG,C,8,EL")
      (footprint "eagle-import:SOP65")
      (libsource (lib "eagle-import") (part "TB6612FNG,C,8,EL"))
    )
    (comp (ref "VD13")
      (value "NUP1301")
      (footprint "eagle-import:SOT23")
      (libsource (lib "eagle-import") (part "ESD_PROTECTIONSOT123"))
    )
    (comp (ref "VD14")
      (value "NUP1301")
      (footprint "eagle-import:SOT23")
      (libsource (lib "eagle-import") (part "ESD_PROTECTIONSOT123"))
    )
    (comp (ref "VD15")
      (value "5819")
      (footprint "eagle-import:SOD123")
      (libsource (lib "eagle-import") (part "DIODESOD-123"))
    )
    (comp (ref "VD16")
      (value "5819")
      (footprint "eagle-import:SOD123")
      (libsource (lib "eagle-import") (part "DIODESOD-123"))
    )
    (comp (ref "X15")
      (value "DUPON4")
      (footprint "eagle-import:1X04DUPON")
      (libsource (lib "eagle-import") (part "1X4DUPON"))
    )
    (comp (ref "Z2")
      (value "8MHz")
      (footprint "eagle-import:CRYSTAL-SMD-3.2X2.5MM")
      (libsource (lib "eagle-import") (part "CRYSTAL4FOOT"))
    )
    (comp (ref "ZD20")
      (value "3V3")
      (footprint "eagle-import:MINIMELF")
      (libsource (lib "eagle-import") (part "ZENER-DIODESMINIMELF"))
    )
  )
  (nets
    (net (code "1") (name "3.3V") (class "Default")
      (node (ref "C9") (pin "P$2") (pinfunction "P$2_P$2") (pintype "bidirectional"))
      (node (ref "LED1") (pin "P$2") (pinfunction "A_P$2") (pintype "passive"))
      (node (ref "R12") (pin "P$2") (pinfunction "P$2_P$2") (pintype "bidirectional"))
      (node (ref "R2") (pin "P$1") (pinfunction "P$1_P$1") (pintype "bidirectional"))
      (node (ref "R27") (pin "P$2") (pinfunction "P$2_P$2") (pintype "bidirectional"))
      (node (ref "R42") (pin "P$1") (pinfunction "P$1_P$1") (pintype "bidirectional"))
      (node (ref "R57") (pin "P$2") (pinfunction "P$2_P$2") (pintype "bidirectional"))
      (node (ref "R58") (pin "P$2") (pinfunction "P$2_P$2") (pintype "bidirectional"))
      (node (ref "R59") (pin "P$1") (pinfunction "P$1_P$1") (pintype "bidirectional"))
      (node (ref "R60") (pin "P$1") (pinfunction "P$1_P$1") (pintype "bidirectional"))
      (node (ref "R61") (pin "P$1") (pinfunction "P$1_P$1") (pintype "bidirectional"))
      (node (ref "R8") (pin "P$2") (pinfunction "P$2_P$2") (pintype "bidirectional"))
      (node (ref "U5") (pin "4") (pinfunction "OUT_4") (pintype "passive"))
      (node (ref "VD10") (pin "2") (pinfunction "VCC_2") (pintype "bidirectional"))
      (node (ref "VD11") (pin "2") (pinfunction "VCC_2") (pintype "bidirectional"))
      (node (ref "VD12") (pin "2") (pinfunction "VCC_2") (pintype "bidirectional"))
      (node (ref "VD13") (pin "2") (pinfunction "VCC_2") (pintype "bidirectional"))
      (node (ref "VD14") (pin "2") (pinfunction "VCC_2") (pintype "bidirectional"))
      (node (ref "VD15") (pin "C") (pinfunction "C_C") (pintype "passive"))
      (node (ref "VD17") (pin "2") (pinfunction "VCC_2") (pintype "bidirectional"))
      (node (ref "VD18") (pin "2") (pinfunction "VCC_2") (pintype "bidirectional"))
      (node (ref "VD19") (pin "2") (pinfunction "VCC_2") (pintype "bidirectional"))
      (node (ref "VD2") (pin "2") (pinfunction "VCC_2") (pintype "bidirectional"))
      (node (ref "VD20") (pin "2") (pinfunction "VCC_2") (pintype "bidirectional"))
      (node (ref "VD21") (pin "2") (pinfunction "VCC_2") (pintype "bidirectional"))
      (node (ref "VD22") (pin "2") (pinfunction "VCC_2") (pintype "bidirectional"))
      (node (ref "VD3") (pin "2") (pinfunction "VCC_2") (pintype "bidirectional"))
      (node (ref "VD9") (pin "2") (pinfunction "VCC_2") (pintype "bidirectional"))
      (node (ref "X4") (pin "5") (pinfunction "5_5") (pintype "passive"))
      (node (ref "X5") (pin "5") (pinfunction "5_5") (pintype "passive"))
      (node (ref "X6") (pin "5") (pinfunction "5_5") (pintype "passive"))
      (node (ref "X7") (pin "5") (pinfunction "5_5") (pintype "passive"))
      (node (ref "ZD20") (pin "C") (pinfunction "C_C") (pintype "passive"))
    )
    (net (code "2") (name "3.3V_S") (class "Default")
      (node (ref "VD15") (pin "A") (pinfunction "A_A") (pintype "passive"))
      (node (ref "VD16") (pin "A") (pinfunction "A_A") (pintype "passive"))
      (node (ref "X15") (pin "1") (pinfunction "1_1") (pintype "passive"))
    )
    (net (code "3") (name "5V") (class "Default")
      (node (ref "C18") (pin "P$2") (pinfunction "P$2_P$2") (pintype "bidirectional"))
      (node (ref "C19") (pin "P$2") (pinfunction "P$2_P$2") (pintype "bidirectional"))
      (node (ref "C5") (pin "P$2") (pinfunction "P$2_P$2") (pintype "bidirectional"))
      (node (ref "C6") (pin "P$2") (pinfunction "P$2_P$2") (pintype "bidirectional"))
      (node (ref "C7") (pin "P$2") (pinfunction "P$2_P$2") (pintype "bidirectional"))
      (node (ref "C8") (pin "P$2") (pinfunction "P$2_P$2") (pintype "bidirectional"))
      (node (ref "R1") (pin "P$1") (pinfunction "P$1_P$1") (pintype "bidirectional"))
      (node (ref "U4") (pin "+O") (pinfunction "+V_OUT_+O") (pintype "bidirectional"))
      (node (ref "U5") (pin "3") (pinfunction "IN_3") (pintype "input"))
      (node (ref "USB1") (pin "1") (pinfunction "1_1") (pintype "passive"))
      (node (ref "VD1") (pin "C") (pinfunction "C_C") (pintype "passive"))
      (node (ref "VD4") (pin "C") (pinfunction "C_C") (pintype "passive"))
      (node (ref "VD5") (pin "C") (pinfunction "C_C") (pintype "passive"))
      (node (ref "X1") (pin "3") (pinfunction "3_3") (pintype "passive"))
      (node (ref "X13") (pin "1") (pinfunction "1_1") (pintype "passive"))
      (node (ref "X14") (pin "1") (pinfunction "1_1") (pintype "passive"))
      (node (ref "X2") (pin "3") (pinfunction "3_3") (pintype "passive"))
      (node (ref "ZD2") (pin "C") (pinfunction "C_C") (pintype "passive"))
    )
    (net (code "4") (name "BOOT0") (class "Default")
      (node (ref "R63") (pin "P$2") (pinfunction "P$2_P$2") (pintype "bidirectional"))
      (node (ref "U2") (pin "44") (pinfunction "BOOT0_44") (pintype "input"))
      (node (ref "VD16") (pin "C") (pinfunction "C_C") (pintype "passive"))
    )
    (net (code "5") (name "BOOT_ESP") (class "Default")
      (node (ref "R18") (pin "P$1") (pinfunction "P$1_P$1") (pintype "bidirectional"))
      (node (ref "R28") (pin "P$2") (pinfunction "P$2_P$2") (pintype "bidirectional"))
      (node (ref "R60") (pin "P$2") (pinfunction "P$2_P$2") (pintype "bidirectional"))
      (node (ref "U1") (pin "25") (pinfunction "IO0_25") (pintype "bidirectional"))
    )
    (net (code "6") (name "CAN_H") (class "Default")
      (node (ref "U3") (pin "7") (pinfunction "CANH_7") (pintype "bidirectional"))
      (node (ref "X1") (pin "1") (pinfunction "1_1") (pintype "passive"))
      (node (ref "X2") (pin "1") (pinfunction "1_1") (pintype "passive"))
    )
    (net (code "7") (name "CAN_L") (class "Default")
      (node (ref "U3") (pin "6") (pinfunction "CANL_6") (pintype "bidirectional"))
      (node (ref "X1") (pin "2") (pinfunction "2_2") (pintype "passive"))
      (node (ref "X2") (pin "2") (pinfunction "2_2") (pintype "passive"))
    )
    (net (code "8") (name "CAN_RX") (class "Default")
      (node (ref "U1") (pin "37") (pinfunction "IO23_37") (pintype "bidirectional"))
      (node (ref "U3") (pin "4") (pinfunction "RXD_4") (pintype "bidirectional"))
    )
    (net (code "9") (name "CAN_TX") (class "Default")
      (node (ref "U1") (pin "31") (pinfunction "IO19_31") (pintype "bidirectional"))
      (node (ref "U3") (pin "1") (pinfunction "TXD_1") (pintype "bidirectional"))
    )
    (net (code "10") (name "D+") (class "Default")
      (node (ref "U7") (pin "5") (pinfunction "UD+_5") (pintype "bidirectional"))
      (node (ref "USB2") (pin "P$3.D+") (pinfunction "3_P$3.D+") (pintype "passive"))
      (node (ref "VD3") (pin "3") (pinfunction "I/O_3") (pintype "bidirectional"))
    )
    (net (code "11") (name "D-") (class "Default")
      (node (ref "U7") (pin "6") (pinfunction "UD-_6") (pintype "bidirectional"))
      (node (ref "USB2") (pin "P$2.D-") (pinfunction "2_P$2.D-") (pintype "passive"))
      (node (ref "VD2") (pin "3") (pinfunction "I/O_3") (pintype "bidirectional"))
    )
    (net (code "12") (name "DCLK") (class "Default")
      (node (ref "U2") (pin "37") (pinfunction "PA14_37") (pintype "bidirectional"))
      (node (ref "VD14") (pin "3") (pinfunction "I/O_3") (pintype "bidirectional"))
      (node (ref "X15") (pin "3") (pinfunction "3_3") (pintype "passive"))
    )
    (net (code "13") (name "DIO") (class "Default")
      (node (ref "U2") (pin "34") (pinfunction "PA13_34") (pintype "bidirectional"))
      (node (ref "VD13") (pin "3") (pinfunction "I/O_3") (pintype "bidirectional"))
      (node (ref "X15") (pin "4") (pinfunction "4_4") (pintype "passive"))
    )
    (net (code "14") (name "D_AIN_1") (class "Default")
      (node (ref "U2") (pin "11") (pinfunction "PA1_11") (pintype "bidirectional"))
      (node (ref "U8") (pin "21") (pinfunction "AIN1_21") (pintype "input"))
    )
    (net (code "15") (name "D_AIN_2") (class "Default")
      (node (ref "U2") (pin "10") (pinfunction "PA0_WKUP_10") (pintype "bidirectional"))
      (node (ref "U8") (pin "22") (pinfunction "AIN2_22") (pintype "input"))
    )
    (net (code "16") (name "D_AIN_3") (class "Default")
      (node (ref "U2") (pin "17") (pinfunction "PA7_17") (pintype "bidirectional"))
      (node (ref "U9") (pin "21") (pinfunction "AIN1_21") (pintype "input"))
    )
    (net (code "17") (name "D_AIN_4") (class "Default")
      (node (ref "U2") (pin "16") (pinfunction "PA6_16") (pintype "bidirectional"))
      (node (ref "U9") (pin "22") (pinfunction "AIN2_22") (pintype "input"))
    )
    (net (code "18") (name "D_BIN_1") (class "Default")
      (node (ref "U2") (pin "14") (pinfunction "PA4_14") (pintype "bidirectional"))
      (node (ref "U8") (pin "17") (pinfunction "BIN1_17") (pintype "input"))
    )
    (net (code "19") (name "D_BIN_2") (class "Default")
      (node (ref "U2") (pin "15") (pinfunction "PA5_15") (pintype "bidirectional"))
      (node (ref "U8") (pin "16") (pinfunction "BIN2_16") (pintype "input"))
    )
    (net (code "20") (name "D_BIN_3") (class "Default")
      (node (ref "U2") (pin "3") (pinfunction "PC14-OSC32_IN_3") (pintype "bidirectional"))
      (node (ref "U9") (pin "17") (pinfunction "BIN1_17") (pintype "input"))
    )
    (net (code "21") (name "D_BIN_4") (class "Default")
      (node (ref "U2") (pin "2") (pinfunction "PC13-TAMPER-RTC_2") (pintype "bidirectional"))
      (node (ref "U9") (pin "16") (pinfunction "BIN2_16") (pintype "input"))
    )
    (net (code "22") (name "D_OUT_1") (class "Default")
      (node (ref "R29") (pin "P$1") (pinfunction "P$1_P$1") (pintype "bidirectional"))
      (node (ref "U2") (pin "28") (pinfunction "PB15_28") (pintype "bidirectional"))
    )
    (net (code "23") (name "D_OUT_2") (class "Default")
      (node (ref "R30") (pin "P$2") (pinfunction "P$2_P$2") (pintype "bidirectional"))
      (node (ref "U2") (pin "27") (pinfunction "PB14_27") (pintype "bidirectional"))
    )
    (net (code "24") (name "D_OUT_3") (class "Default")
      (node (ref "R36") (pin "P$2") (pinfunction "P$2_P$2") (pintype "bidirectional"))
      (node (ref "U2") (pin "26") (pinfunction "PB13_26") (pintype "bidirectional"))
    )
    (net (code "25") (name "D_OUT_4") (class "Default")
      (node (ref "R32") (pin "P$2") (pinfunction "P$2_P$2") (pintype "bidirectional"))
      (node (ref "U2") (pin "25") (pinfunction "PB12_25") (pintype "bidirectional"))
    )
    (net (code "26") (name "D_OUT_5") (class "Default")
      (node (ref "R43") (pin "P$2") (pinfunction "P$2_P$2") (pintype "bidirectional"))
      (node (ref "U2") (pin "33") (pinfunction "PA12_33") (pintype "bidirectional"))
    )
    (net (code "27") (name "ENC_1") (class "Default")
      (node (ref "R71") (pin "P$1") (pinfunction "P$1_P$1") (pintype "bidirectional"))
      (node (ref "U2") (pin "43") (pinfunction "PB7_43") (pintype "bidirectional"))
      (node (ref "VD11") (pin "3") (pinfunction "I/O_3") (pintype "bidirectional"))
      (node (ref "ZD13") (pin "C") (pinfunction "C_C") (pintype "passive"))
    )
    (net (code "28") (name "ENC_2") (class "Default")
      (node (ref "R70") (pin "P$1") (pinfunction "P$1_P$1") (pintype "bidirectional"))
      (node (ref "U2") (pin "42") (pinfunction "PB6_42") (pintype "bidirectional"))
      (node (ref "VD12") (pin "3") (pinfunction "I/O_3") (pintype "bidirectional"))
      (node (ref "ZD14") (pin "C") (pinfunction "C_C") (pintype "passive"))
    )
    (net (code "29") (name "ENC_3") (class "Default")
      (node (ref "R49") (pin "P$1") (pinfunction "P$1_P$1") (pintype "bidirectional"))
      (node (ref "U2") (pin "41") (pinfunction "PB5_41") (pintype "bidirectional"))
      (node (ref "VD17") (pin "3") (pinfunction "I/O_3") (pintype "bidirectional"))
      (node (ref "ZD7") (pin "C") (pinfunction "C_C") (pintype "passive"))
    )
    (net (code "30") (name "ENC_4") (class "Default")
      (node (ref "R50") (pin "P$1") (pinfunction "P$1_P$1") (pintype "bidirectional"))
      (node (ref "U2") (pin "40") (pinfunction "PB4_40") (pintype "bidirectional"))
      (node (ref "VD18") (pin "3") (pinfunction "I/O_3") (pintype "bidirectional"))
      (node (ref "ZD4") (pin "C") (pinfunction "C_C") (pintype "passive"))
    )
    (net (code "31") (name "ENC_5") (class "Default")
      (node (ref "R51") (pin "P$1") (pinfunction "P$1_P$1") (pintype "bidirectional"))
      (node (ref "U2") (pin "39") (pinfunction "PB3_39") (pintype "bidirectional"))
      (node (ref "VD19") (pin "3") (pinfunction "I/O_3") (pintype "bidirectional"))
      (node (ref "ZD8") (pin "C") (pinfunction "C_C") (pintype "passive"))
    )
    (net (code "32") (name "ENC_6") (class "Default")
      (node (ref "R52") (pin "P$1") (pinfunction "P$1_P$1") (pintype "bidirectional"))
      (node (ref "U2") (pin "38") (pinfunction "PA15_38") (pintype "bidirectional"))
      (node (ref "VD20") (pin "3") (pinfunction "I/O_3") (pintype "bidirectional"))
      (node (ref "ZD9") (pin "C") (pinfunction "C_C") (pintype "passive"))
    )
    (net (code "33") (name "ENC_7") (class "Default")
      (node (ref "R54") (pin "P$1") (pinfunction "P$1_P$1") (pintype "bidirectional"))
      (node (ref "U2") (pin "30") (pinfunction "PA9_30") (pintype "bidirectional"))
      (node (ref "VD21") (pin "3") (pinfunction "I/O_3") (pintype "bidirectional"))
      (node (ref "ZD10") (pin "C") (pinfunction "C_C") (pintype "passive"))
    )
    (net (code "34") (name "ENC_8") (class "Default")
      (node (ref "R53") (pin "P$1") (pinfunction "P$1_P$1") (pintype "bidirectional"))
      (node (ref "U2") (pin "29") (pinfunction "PA8_29") (pintype "bidirectional"))
      (node (ref "VD22") (pin "3") (pinfunction "I/O_3") (pintype "bidirectional"))
      (node (ref "ZD11") (pin "C") (pinfunction "C_C") (pintype "passive"))
    )
    (net (code "35") (name "GND") (class "Default")
      (node (ref "C1") (pin "P$1") (pinfunction "P$1_P$1") (pintype "bidirectional"))
      (node (ref "C10") (pin "P$1") (pinfunction "P$1_P$1") (pintype "bidirectional"))
      (node (ref "C11") (pin "P$1") (pinfunction "P$1_P$1") (pintype "bidirectional"))
      (node (ref "C12") (pin "P$1") (pinfunction "P$1_P$1") (pintype "bidirectional"))
      (node (ref "C13") (pin "P$1") (pinfunction "P$1_P$1") (pintype "bidirectional"))
      (node (ref "C14") (pin "P$1") (pinfunction "P$1_P$1") (pintype "bidirectional"))
      (node (ref "C15") (pin "P$2") (pinfunction "P$2_P$2") (pintype "bidirectional"))
      (node (ref "C17") (pin "P$1") (pinfunction "P$1_P$1") (pintype "bidirectional"))
      (node (ref "C18") (pin "P$1") (pinfunction "P$1_P$1") (pintype "bidirectional"))
      (node (ref "C19") (pin "P$1") (pinfunction "P$1_P$1") (pintype "bidirectional"))
      (node (ref "C2") (pin "P$1") (pinfunction "P$1_P$1") (pintype "bidirectional"))
      (node (ref "C20") (pin "P$1") (pinfunction "P$1_P$1") (pintype "bidirectional"))
      (node (ref "C21") (pin "P$1") (pinfunction "P$1_P$1") (pintype "bidirectional"))
      (node (ref "C22") (pin "P$1") (pinfunction "P$1_P$1") (pintype "bidirectional"))
      (node (ref "C23") (pin "P$1") (pinfunction "P$1_P$1") (pintype "bidirectional"))
      (node (ref "C24") (pin "P$1") (pinfunction "P$1_P$1") (pintype "bidirectional"))
      (node (ref "C25") (pin "P$1") (pinfunction "P$1_P$1") (pintype "bidirectional"))
      (node (ref "C26") (pin "P$1") (pinfunction "P$1_P$1") (pintype "bidirectional"))
      (node (ref "C27") (pin "P$1") (pinfunction "P$1_P$1") (pintype "bidirectional"))
      (node (ref "C28") (pin "P$1") (pinfunction "P$1_P$1") (pintype "bidirectional"))
      (node (ref "C29") (pin "P$1") (pinfunction "P$1_P$1") (pintype "bidirectional"))
      (node (ref "C3") (pin "P$1") (pinfunction "P$1_P$1") (pintype "bidirectional"))
      (node (ref "C30") (pin "P$1") (pinfunction "P$1_P$1") (pintype "bidirectional"))
      (node (ref "C31") (pin "P$1") (pinfunction "P$1_P$1") (pintype "bidirectional"))
      (node (ref "C32") (pin "P$1") (pinfunction "P$1_P$1") (pintype "bidirectional"))
      (node (ref "C33") (pin "P$1") (pinfunction "P$1_P$1") (pintype "bidirectional"))
      (node (ref "C34") (pin "P$1") (pinfunction "P$1_P$1") (pintype "bidirectional"))
      (node (ref "C35") (pin "P$1") (pinfunction "P$1_P$1") (pintype "bidirectional"))
      (node (ref "C36") (pin "P$1") (pinfunction "P$1_P$1") (pintype "bidirectional"))
      (node (ref "C37") (pin "P$1") (pinfunction "P$1_P$1") (pintype "bidirectional"))
      (node (ref "C38") (pin "P$1") (pinfunction "P$1_P$1") (pintype "bidirectional"))
      (node (ref "C39") (pin "P$1") (pinfunction "P$1_P$1") (pintype "bidirectional"))
      (node (ref "C4") (pin "P$1") (pinfunction "P$1_P$1") (pintype "bidirectional"))
      (node (ref "C40") (pin "P$1") (pinfunction "P$1_P$1") (pintype "bidirectional"))
      (node (ref "C5") (pin "P$1") (pinfunction "P$1_P$1") (pintype "bidirectional"))
      (node (ref "C6") (pin "P$1") (pinfunction "P$1_P$1") (pintype "bidirectional"))
      (node (ref "C7") (pin "P$1") (pinfunction "P$1_P$1") (pintype "bidirectional"))
      (node (ref "C8") (pin "P$1") (pinfunction "P$1_P$1") (pintype "bidirectional"))
      (node (ref "C9") (pin "P$1") (pinfunction "P$1_P$1") (pintype "bidirectional"))
      (node (ref "R10") (pin "P$1") (pinfunction "P$1_P$1") (pintype "bidirectional"))
      (node (ref "R11") (pin "P$1") (pinfunction "P$1_P$1") (pintype "bidirectional"))
      (node (ref "R15") (pin "P$2") (pinfunction "P$2_P$2") (pintype "bidirectional"))
      (node (ref "R19") (pin "P$1") (pinfunction "P$1_P$1") (pintype "bidirectional"))
      (node (ref "R21") (pin "P$2") (pinfunction "P$2_P$2") (pintype "bidirectional"))
      (node (ref "R23") (pin "P$2") (pinfunction "P$2_P$2") (pintype "bidirectional"))
      (node (ref "R25") (pin "P$2") (pinfunction "P$2_P$2") (pintype "bidirectional"))
      (node (ref "R31") (pin "P$1") (pinfunction "P$1_P$1") (pintype "bidirectional"))
      (node (ref "R34") (pin "P$1") (pinfunction "P$1_P$1") (pintype "bidirectional"))
      (node (ref "R37") (pin "P$1") (pinfunction "P$1_P$1") (pintype "bidirectional"))
      (node (ref "R44") (pin "P$1") (pinfunction "P$1_P$1") (pintype "bidirectional"))
      (node (ref "R46") (pin "P$1") (pinfunction "P$1_P$1") (pintype "bidirectional"))
      (node (ref "R6") (pin "P$1") (pinfunction "P$1_P$1") (pintype "bidirectional"))
      (node (ref "R62") (pin "P$2") (pinfunction "P$2_P$2") (pintype "bidirectional"))
      (node (ref "R63") (pin "P$1") (pinfunction "P$1_P$1") (pintype "bidirectional"))
      (node (ref "R7") (pin "P$2") (pinfunction "P$2_P$2") (pintype "bidirectional"))
      (node (ref "R9") (pin "P$1") (pinfunction "P$1_P$1") (pintype "bidirectional"))
      (node (ref "S1") (pin "3") (pinfunction "3_3") (pintype "passive"))
      (node (ref "S1") (pin "4") (pinfunction "4_4") (pintype "passive"))
      (node (ref "S2") (pin "3") (pinfunction "3_3") (pintype "passive"))
      (node (ref "S2") (pin "4") (pinfunction "4_4") (pintype "passive"))
      (node (ref "S3") (pin "3") (pinfunction "3_3") (pintype "passive"))
      (node (ref "U1") (pin "1") (pinfunction "GND_1") (pintype "bidirectional"))
      (node (ref "U1") (pin "15") (pinfunction "GND_15") (pintype "bidirectional"))
      (node (ref "U1") (pin "38") (pinfunction "GND_38") (pintype "bidirectional"))
      (node (ref "U1") (pin "GND") (pinfunction "GND_GND") (pintype "bidirectional"))
      (node (ref "U10") (pin "18") (pinfunction "GND_18") (pintype "power_in"))
      (node (ref "U10") (pin "20") (pinfunction "RESV_20_20") (pintype "passive"))
      (node (ref "U2") (pin "23") (pinfunction "VSS_23") (pintype "power_in"))
      (node (ref "U2") (pin "35") (pinfunction "VSS_35") (pintype "power_in"))
      (node (ref "U2") (pin "47") (pinfunction "VSS_47") (pintype "power_in"))
      (node (ref "U2") (pin "8") (pinfunction "VSSA_8") (pintype "power_in"))
      (node (ref "U3") (pin "2") (pinfunction "GND_2") (pintype "bidirectional"))
      (node (ref "U3") (pin "8") (pinfunction "RS_8") (pintype "bidirectional"))
      (node (ref "U4") (pin "-I") (pinfunction "GND_IN_-I") (pintype "bidirectional"))
      (node (ref "U4") (pin "-O") (pinfunction "GND_OUT_-O") (pintype "bidirectional"))
      (node (ref "U6") (pin "4") (pinfunction "GND_4") (pintype "power_in"))
      (node (ref "U7") (pin "1") (pinfunction "GND_1") (pintype "power_in"))
      (node (ref "USB1") (pin "4") (pinfunction "4_4") (pintype "passive"))
      (node (ref "USB1") (pin "SH1") (pinfunction "SHIELD_SH1") (pintype "passive"))
      (node (ref "USB1") (pin "SH2") (pinfunction "SHIELD_SH2") (pintype "passive"))
      (node (ref "USB2") (pin "P$4.GND") (pinfunction "4_P$4.GND") (pintype "passive"))
      (node (ref "USB2") (pin "P$5.SH2") (pinfunction "SHIELD_P$5.SH2") (pintype "passive"))
      (node (ref "USB2") (pin "P$6.SH1") (pinfunction "SHIELD_P$6.SH1") (pintype "passive"))
      (node (ref "VD10") (pin "1") (pinfunction "GND_1") (pintype "bidirectional"))
      (node (ref "VD11") (pin "1") (pinfunction "GND_1") (pintype "bidirectional"))
      (node (ref "VD12") (pin "1") (pinfunction "GND_1") (pintype "bidirectional"))
      (node (ref "VD13") (pin "1") (pinfunction "GND_1") (pintype "bidirectional"))
      (node (ref "VD14") (pin "1") (pinfunction "GND_1") (pintype "bidirectional"))
      (node (ref "VD17") (pin "1") (pinfunction "GND_1") (pintype "bidirectional"))
      (node (ref "VD18") (pin "1") (pinfunction "GND_1") (pintype "bidirectional"))
      (node (ref "VD19") (pin "1") (pinfunction "GND_1") (pintype "bidirectional"))
      (node (ref "VD2") (pin "1") (pinfunction "GND_1") (pintype "bidirectional"))
      (node (ref "VD20") (pin "1") (pinfunction "GND_1") (pintype "bidirectional"))
      (node (ref "VD21") (pin "1") (pinfunction "GND_1") (pintype "bidirectional"))
      (node (ref "VD22") (pin "1") (pinfunction "GND_1") (pintype "bidirectional"))
      (node (ref "VD3") (pin "1") (pinfunction "GND_1") (pintype "bidirectional"))
      (node (ref "VD9") (pin "1") (pinfunction "GND_1") (pintype "bidirectional"))
      (node (ref "VT1") (pin "2") (pinfunction "E_2") (pintype "passive"))
      (node (ref "VT2") (pin "2") (pinfunction "E_2") (pintype "passive"))
      (node (ref "VT3") (pin "2") (pinfunction "E_2") (pintype "passive"))
      (node (ref "VT4") (pin "2") (pinfunction "E_2") (pintype "passive"))
      (node (ref "VT7") (pin "2") (pinfunction "E_2") (pintype "passive"))
      (node (ref "X1") (pin "4") (pinfunction "4_4") (pintype "passive"))
      (node (ref "X15") (pin "2") (pinfunction "2_2") (pintype "passive"))
      (node (ref "X2") (pin "4") (pinfunction "4_4") (pintype "passive"))
      (node (ref "X3") (pin "1") (pinfunction "1_1") (pintype "passive"))
      (node (ref "X3") (pin "2") (pinfunction "2_2") (pintype "passive"))
      (node (ref "X4") (pin "6") (pinfunction "6_6") (pintype "passive"))
      (node (ref "X5") (pin "6") (pinfunction "6_6") (pintype "passive"))
      (node (ref "X6") (pin "6") (pinfunction "6_6") (pintype "passive"))
      (node (ref "X7") (pin "6") (pinfunction "6_6") (pintype "passive"))
      (node (ref "X8") (pin "3") (pinfunction "3_3") (pintype "passive"))
      (node (ref "X9") (pin "3") (pinfunction "3_3") (pintype "passive"))
      (node (ref "ZD1") (pin "A") (pinfunction "A_A") (pintype "passive"))
      (node (ref "ZD10") (pin "A") (pinfunction "A_A") (pintype "passive"))
      (node (ref "ZD11") (pin "A") (pinfunction "A_A") (pintype "passive"))
      (node (ref "ZD13") (pin "A") (pinfunction "A_A") (pintype "passive"))
      (node (ref "ZD14") (pin "A") (pinfunction "A_A") (pintype "passive"))
      (node (ref "ZD2") (pin "A") (pinfunction "A_A") (pintype "passive"))
      (node (ref "ZD20") (pin "A") (pinfunction "A_A") (pintype "passive"))
      (node (ref "ZD3") (pin "A") (pinfunction "A_A") (pintype "passive"))
      (node (ref "ZD4") (pin "A") (pinfunction "A_A") (pintype "passive"))
      (node (ref "ZD5") (pin "A") (pinfunction "A_A") (pintype "passive"))
      (node (ref "ZD6") (pin "A") (pinfunction "A_A") (pintype "passive"))
      (node (ref "ZD7") (pin "A") (pinfunction "A_A") (pintype "passive"))
      (node (ref "ZD8") (pin "A") (pinfunction "A_A") (pintype "passive"))
      (node (ref "ZD9") (pin "A") (pinfunction "A_A") (pintype "passive"))
    )
    (net (code "36") (name "GND_D") (class "Default")
      (node (ref "C16") (pin "P$1") (pinfunction "P$1_P$1") (pintype "bidirectional"))
      (node (ref "C30") (pin "P$2") (pinfunction "P$2_P$2") (pintype "bidirectional"))
      (node (ref "C41") (pin "P$1") (pinfunction "P$1_P$1") (pintype "bidirectional"))
      (node (ref "R44") (pin "P$2") (pinfunction "P$2_P$2") (pintype "bidirectional"))
      (node (ref "U6") (pin "3") (pinfunction "+IN1_3") (pintype "input"))
      (node (ref "U8") (pin "10") (pinfunction "PGND2_10") (pintype "passive"))
      (node (ref "U8") (pin "18") (pinfunction "GND_18") (pintype "passive"))
      (node (ref "U8") (pin "3") (pinfunction "PGND1_3") (pintype "passive"))
      (node (ref "U8") (pin "4") (pinfunction "PGND1_4") (pintype "passive"))
      (node (ref "U8") (pin "9") (pinfunction "PGND2_9") (pintype "passive"))
      (node (ref "U9") (pin "10") (pinfunction "PGND2_10") (pintype "passive"))
      (node (ref "U9") (pin "18") (pinfunction "GND_18") (pintype "passive"))
      (node (ref "U9") (pin "3") (pinfunction "PGND1_3") (pintype "passive"))
      (node (ref "U9") (pin "4") (pinfunction "PGND1_4") (pintype "passive"))
      (node (ref "U9") (pin "9") (pinfunction "PGND2_9") (pintype "passive"))
    )
    (net (code "37") (name "INT") (class "Default")
      (node (ref "R35") (pin "P$1") (pinfunction "P$1_P$1") (pintype "bidirectional"))
      (node (ref "U1") (pin "27") (pinfunction "IO16_27") (pintype "bidirectional"))
    )
    (net (code "38") (name "I_CDC") (class "Default")
      (node (ref "C31") (pin "P$2") (pinfunction "P$2_P$2") (pintype "bidirectional"))
      (node (ref "R26") (pin "P$2") (pinfunction "P$2_P$2") (pintype "bidirectional"))
      (node (ref "U1") (pin "5") (pinfunction "SENSOR_VN_5") (pintype "input"))
      (node (ref "U6") (pin "1") (pinfunction "OUT1_1") (pintype "output"))
    )
    (net (code "39") (name "M_1_1") (class "Default")
      (node (ref "U8") (pin "1") (pinfunction "AO1_1") (pintype "output"))
      (node (ref "U8") (pin "2") (pinfunction "AO1_2") (pintype "output"))
      (node (ref "X6") (pin "2") (pinfunction "2_2") (pintype "passive"))
    )
    (net (code "40") (name "M_1_2") (class "Default")
      (node (ref "U8") (pin "5") (pinfunction "AO2_5") (pintype "output"))
      (node (ref "U8") (pin "6") (pinfunction "AO2_6") (pintype "output"))
      (node (ref "X6") (pin "1") (pinfunction "1_1") (pintype "passive"))
    )
    (net (code "41") (name "M_2_1") (class "Default")
      (node (ref "U8") (pin "11") (pinfunction "BO1_11") (pintype "output"))
      (node (ref "U8") (pin "12") (pinfunction "BO1_12") (pintype "output"))
      (node (ref "X7") (pin "1") (pinfunction "1_1") (pintype "passive"))
    )
    (net (code "42") (name "M_2_2") (class "Default")
      (node (ref "U8") (pin "7") (pinfunction "BO2_7") (pintype "output"))
      (node (ref "U8") (pin "8") (pinfunction "BO2_8") (pintype "output"))
      (node (ref "X7") (pin "2") (pinfunction "2_2") (pintype "passive"))
    )
    (net (code "43") (name "M_3_1") (class "Default")
      (node (ref "U9") (pin "1") (pinfunction "AO1_1") (pintype "output"))
      (node (ref "U9") (pin "2") (pinfunction "AO1_2") (pintype "output"))
      (node (ref "X4") (pin "2") (pinfunction "2_2") (pintype "passive"))
    )
    (net (code "44") (name "M_3_2") (class "Default")
      (node (ref "U9") (pin "5") (pinfunction "AO2_5") (pintype "output"))
      (node (ref "U9") (pin "6") (pinfunction "AO2_6") (pintype "output"))
      (node (ref "X4") (pin "1") (pinfunction "1_1") (pintype "passive"))
    )
    (net (code "45") (name "M_4_1") (class "Default")
      (node (ref "U9") (pin "11") (pinfunction "BO1_11") (pintype "output"))
      (node (ref "U9") (pin "12") (pinfunction "BO1_12") (pintype "output"))
      (node (ref "X5") (pin "1") (pinfunction "1_1") (pintype "passive"))
    )
    (net (code "46") (name "M_4_2") (class "Default")
      (node (ref "U9") (pin "7") (pinfunction "BO2_7") (pintype "output"))
      (node (ref "U9") (pin "8") (pinfunction "BO2_8") (pintype "output"))
      (node (ref "X5") (pin "2") (pinfunction "2_2") (pintype "passive"))
    )
    (net (code "47") (name "Net-(C1-PadP$2)") (class "Default")
      (node (ref "C1") (pin "P$2") (pinfunction "P$2_P$2") (pintype "bidirectional"))
      (node (ref "L1") (pin "1") (pinfunction "1_1") (pintype "passive"))
      (node (ref "X8") (pin "2") (pinfunction "2_2") (pintype "passive"))
      (node (ref "X9") (pin "2") (pinfunction "2_2") (pintype "passive"))
    )
    (net (code "48") (name "Net-(C13-PadP$2)") (class "Default")
      (node (ref "C13") (pin "P$2") (pinfunction "P$2_P$2") (pintype "bidirectional"))
      (node (ref "R17") (pin "P$1") (pinfunction "P$1_P$1") (pintype "bidirectional"))
      (node (ref "S1") (pin "1") (pinfunction "1_1") (pintype "passive"))
    )
    (net (code "49") (name "Net-(C40-PadP$2)") (class "Default")
      (node (ref "C40") (pin "P$2") (pinfunction "P$2_P$2") (pintype "bidirectional"))
      (node (ref "R18") (pin "P$2") (pinfunction "P$2_P$2") (pintype "bidirectional"))
      (node (ref "S2") (pin "1") (pinfunction "1_1") (pintype "passive"))
    )
    (net (code "50") (name "Net-(L1-Pad2)") (class "Default")
      (node (ref "L1") (pin "2") (pinfunction "2_2") (pintype "passive"))
      (node (ref "R1") (pin "P$2") (pinfunction "P$2_P$2") (pintype "bidirectional"))
    )
    (net (code "51") (name "Net-(LED1-C)") (class "Default")
      (node (ref "LED1") (pin "P$1") (pinfunction "C_P$1") (pintype "passive"))
      (node (ref "R9") (pin "P$2") (pinfunction "P$2_P$2") (pintype "bidirectional"))
    )
    (net (code "52") (name "Net-(LED2-A)") (class "Default")
      (node (ref "LED2") (pin "P$2") (pinfunction "A_P$2") (pintype "passive"))
      (node (ref "U1") (pin "11") (pinfunction "IO26_11") (pintype "bidirectional"))
    )
    (net (code "53") (name "Net-(LED2-C)") (class "Default")
      (node (ref "LED2") (pin "P$1") (pinfunction "C_P$1") (pintype "passive"))
      (node (ref "R11") (pin "P$2") (pinfunction "P$2_P$2") (pintype "bidirectional"))
    )
    (net (code "54") (name "Net-(LED3-A)") (class "Default")
      (node (ref "LED3") (pin "P$2") (pinfunction "A_P$2") (pintype "passive"))
      (node (ref "U1") (pin "12") (pinfunction "IO27_12") (pintype "bidirectional"))
    )
    (net (code "55") (name "Net-(LED3-C)") (class "Default")
      (node (ref "LED3") (pin "P$1") (pinfunction "C_P$1") (pintype "passive"))
      (node (ref "R10") (pin "P$2") (pinfunction "P$2_P$2") (pintype "bidirectional"))
    )
    (net (code "56") (name "Net-(LED4-A)") (class "Default")
      (node (ref "LED4") (pin "P$2") (pinfunction "A_P$2") (pintype "passive"))
      (node (ref "U2") (pin "31") (pinfunction "PA10_31") (pintype "bidirectional"))
    )
    (net (code "57") (name "Net-(LED4-C)") (class "Default")
      (node (ref "LED4") (pin "P$1") (pinfunction "C_P$1") (pintype "passive"))
      (node (ref "R62") (pin "P$1") (pinfunction "P$1_P$1") (pintype "bidirectional"))
    )
    (net (code "58") (name "Net-(LED5-A)") (class "Default")
      (node (ref "LED5") (pin "P$2") (pinfunction "A_P$2") (pintype "passive"))
      (node (ref "U2") (pin "32") (pinfunction "PA11_32") (pintype "bidirectional"))
    )
    (net (code "59") (name "Net-(LED5-C)") (class "Default")
      (node (ref "LED5") (pin "P$1") (pinfunction "C_P$1") (pintype "passive"))
      (node (ref "R23") (pin "P$1") (pinfunction "P$1_P$1") (pintype "bidirectional"))
    )
    (net (code "60") (name "Net-(R3-PadP$1)") (class "Default")
      (node (ref "R3") (pin "P$1") (pinfunction "P$1_P$1") (pintype "bidirectional"))
      (node (ref "VD1") (pin "A") (pinfunction "A_A") (pintype "passive"))
    )
    (net (code "61") (name "Net-(R4-P$1)") (class "Default")
      (node (ref "R4") (pin "1") (pinfunction "P$1_1") (pintype "bidirectional"))
      (node (ref "X3") (pin "3") (pinfunction "3_3") (pintype "passive"))
      (node (ref "X3") (pin "4") (pinfunction "4_4") (pintype "passive"))
    )
    (net (code "62") (name "Net-(R47-PadP$1)") (class "Default")
      (node (ref "R47") (pin "P$1") (pinfunction "P$1_P$1") (pintype "bidirectional"))
      (node (ref "X8") (pin "1") (pinfunction "1_1") (pintype "passive"))
    )
    (net (code "63") (name "Net-(R48-PadP$1)") (class "Default")
      (node (ref "R48") (pin "P$1") (pinfunction "P$1_P$1") (pintype "bidirectional"))
      (node (ref "X9") (pin "1") (pinfunction "1_1") (pintype "passive"))
    )
    (net (code "64") (name "Net-(R49-PadP$2)") (class "Default")
      (node (ref "R49") (pin "P$2") (pinfunction "P$2_P$2") (pintype "bidirectional"))
      (node (ref "X7") (pin "3") (pinfunction "3_3") (pintype "passive"))
    )
    (net (code "65") (name "Net-(R50-PadP$2)") (class "Default")
      (node (ref "R50") (pin "P$2") (pinfunction "P$2_P$2") (pintype "bidirectional"))
      (node (ref "X7") (pin "4") (pinfunction "4_4") (pintype "passive"))
    )
    (net (code "66") (name "Net-(R51-PadP$2)") (class "Default")
      (node (ref "R51") (pin "P$2") (pinfunction "P$2_P$2") (pintype "bidirectional"))
      (node (ref "X4") (pin "3") (pinfunction "3_3") (pintype "passive"))
    )
    (net (code "67") (name "Net-(R52-PadP$2)") (class "Default")
      (node (ref "R52") (pin "P$2") (pinfunction "P$2_P$2") (pintype "bidirectional"))
      (node (ref "X4") (pin "4") (pinfunction "4_4") (pintype "passive"))
    )
    (net (code "68") (name "Net-(R53-PadP$2)") (class "Default")
      (node (ref "R53") (pin "P$2") (pinfunction "P$2_P$2") (pintype "bidirectional"))
      (node (ref "X5") (pin "4") (pinfunction "4_4") (pintype "passive"))
    )
    (net (code "69") (name "Net-(R54-PadP$2)") (class "Default")
      (node (ref "R54") (pin "P$2") (pinfunction "P$2_P$2") (pintype "bidirectional"))
      (node (ref "X5") (pin "3") (pinfunction "3_3") (pintype "passive"))
    )
    (net (code "70") (name "Net-(R70-PadP$2)") (class "Default")
      (node (ref "R70") (pin "P$2") (pinfunction "P$2_P$2") (pintype "bidirectional"))
      (node (ref "X6") (pin "4") (pinfunction "4_4") (pintype "passive"))
    )
    (net (code "71") (name "Net-(R71-PadP$2)") (class "Default")
      (node (ref "R71") (pin "P$2") (pinfunction "P$2_P$2") (pintype "bidirectional"))
      (node (ref "X6") (pin "3") (pinfunction "3_3") (pintype "passive"))
    )
    (net (code "72") (name "Net-(RX-A)") (class "Default")
      (node (ref "C23") (pin "P$2") (pinfunction "P$2_P$2") (pintype "bidirectional"))
      (node (ref "C24") (pin "P$2") (pinfunction "P$2_P$2") (pintype "bidirectional"))
      (node (ref "C25") (pin "P$2") (pinfunction "P$2_P$2") (pintype "bidirectional"))
      (node (ref "R42") (pin "P$2") (pinfunction "P$2_P$2") (pintype "bidirectional"))
      (node (ref "RX") (pin "P$2") (pinfunction "A_P$2") (pintype "passive"))
      (node (ref "TX") (pin "P$2") (pinfunction "A_P$2") (pintype "passive"))
      (node (ref "U7") (pin "16") (pinfunction "VCC_16") (pintype "power_in"))
      (node (ref "U7") (pin "4") (pinfunction "V3_4") (pintype "power_in"))
    )
    (net (code "73") (name "Net-(RX-C)") (class "Default")
      (node (ref "R38") (pin "P$2") (pinfunction "P$2_P$2") (pintype "bidirectional"))
      (node (ref "RX") (pin "P$1") (pinfunction "C_P$1") (pintype "passive"))
    )
    (net (code "74") (name "Net-(TX-C)") (class "Default")
      (node (ref "R39") (pin "P$2") (pinfunction "P$2_P$2") (pintype "bidirectional"))
      (node (ref "TX") (pin "P$1") (pinfunction "C_P$1") (pintype "passive"))
    )
    (net (code "75") (name "Net-(U1-3V3)") (class "Default")
      (node (ref "C32") (pin "P$2") (pinfunction "P$2_P$2") (pintype "bidirectional"))
      (node (ref "R13") (pin "P$2") (pinfunction "P$2_P$2") (pintype "bidirectional"))
      (node (ref "R16") (pin "P$2") (pinfunction "P$2_P$2") (pintype "bidirectional"))
      (node (ref "R24") (pin "P$1") (pinfunction "P$1_P$1") (pintype "bidirectional"))
      (node (ref "R59") (pin "P$2") (pinfunction "P$2_P$2") (pintype "bidirectional"))
      (node (ref "U1") (pin "2") (pinfunction "3V3_2") (pintype "bidirectional"))
    )
    (net (code "76") (name "Net-(U2-NRST)") (class "Default")
      (node (ref "C15") (pin "P$1") (pinfunction "P$1_P$1") (pintype "bidirectional"))
      (node (ref "R55") (pin "P$1") (pinfunction "P$1_P$1") (pintype "bidirectional"))
      (node (ref "S3") (pin "1") (pinfunction "1_1") (pintype "passive"))
      (node (ref "U2") (pin "7") (pinfunction "NRST_7") (pintype "input"))
    )
    (net (code "77") (name "Net-(U2-PD0_OSC_IN)") (class "Default")
      (node (ref "C33") (pin "P$2") (pinfunction "P$2_P$2") (pintype "bidirectional"))
      (node (ref "U2") (pin "5") (pinfunction "PD0_OSC_IN_5") (pintype "bidirectional"))
      (node (ref "Z2") (pin "3") (pinfunction "2_3") (pintype "passive"))
    )
    (net (code "78") (name "Net-(U2-PD1_OSC_OUT)") (class "Default")
      (node (ref "C14") (pin "P$2") (pinfunction "P$2_P$2") (pintype "bidirectional"))
      (node (ref "U2") (pin "6") (pinfunction "PD1_OSC_OUT_6") (pintype "bidirectional"))
      (node (ref "Z2") (pin "1") (pinfunction "1_1") (pintype "passive"))
    )
    (net (code "79") (name "Net-(U2-VBAT)") (class "Default")
      (node (ref "C34") (pin "P$2") (pinfunction "P$2_P$2") (pintype "bidirectional"))
      (node (ref "C35") (pin "P$2") (pinfunction "P$2_P$2") (pintype "bidirectional"))
      (node (ref "C36") (pin "P$2") (pinfunction "P$2_P$2") (pintype "bidirectional"))
      (node (ref "C37") (pin "P$2") (pinfunction "P$2_P$2") (pintype "bidirectional"))
      (node (ref "C38") (pin "P$2") (pinfunction "P$2_P$2") (pintype "bidirectional"))
      (node (ref "C39") (pin "P$2") (pinfunction "P$2_P$2") (pintype "bidirectional"))
      (node (ref "R55") (pin "P$2") (pinfunction "P$2_P$2") (pintype "bidirectional"))
      (node (ref "R61") (pin "P$2") (pinfunction "P$2_P$2") (pintype "bidirectional"))
      (node (ref "U2") (pin "1") (pinfunction "VBAT_1") (pintype "bidirectional"))
      (node (ref "U2") (pin "24") (pinfunction "VDD_24") (pintype "power_in"))
      (node (ref "U2") (pin "36") (pinfunction "VDD_36") (pintype "power_in"))
      (node (ref "U2") (pin "48") (pinfunction "VDD_48") (pintype "power_in"))
      (node (ref "U2") (pin "9") (pinfunction "VDDA_9") (pintype "power_in"))
    )
    (net (code "80") (name "Net-(U3-VCC)") (class "Default")
      (node (ref "C2") (pin "P$2") (pinfunction "P$2_P$2") (pintype "bidirectional"))
      (node (ref "R2") (pin "P$2") (pinfunction "P$2_P$2") (pintype "bidirectional"))
      (node (ref "U3") (pin "3") (pinfunction "VCC_3") (pintype "bidirectional"))
    )
    (net (code "81") (name "Net-(U5-ADJ{slash}GND)") (class "Default")
      (node (ref "R7") (pin "P$1") (pinfunction "P$1_P$1") (pintype "bidirectional"))
      (node (ref "R8") (pin "P$1") (pinfunction "P$1_P$1") (pintype "bidirectional"))
      (node (ref "U5") (pin "1") (pinfunction "ADJ/GND_1") (pintype "input"))
    )
    (net (code "82") (name "Net-(U6A-+V)") (class "Default")
      (node (ref "R27") (pin "P$1") (pinfunction "P$1_P$1") (pintype "bidirectional"))
      (node (ref "U6") (pin "8") (pinfunction "+V_8") (pintype "power_in"))
    )
    (net (code "83") (name "Net-(U6A--IN1)") (class "Default")
      (node (ref "R19") (pin "P$2") (pinfunction "P$2_P$2") (pintype "bidirectional"))
      (node (ref "R26") (pin "P$1") (pinfunction "P$1_P$1") (pintype "bidirectional"))
      (node (ref "U6") (pin "2") (pinfunction "-IN1_2") (pintype "input"))
    )
    (net (code "84") (name "Net-(U6B-+IN2)") (class "Default")
      (node (ref "U6") (pin "5") (pinfunction "+IN2_5") (pintype "input"))
      (node (ref "U6") (pin "6") (pinfunction "-IN2_6") (pintype "input"))
    )
    (net (code "85") (name "Net-(U7-DTR)") (class "Default")
      (node (ref "R41") (pin "P$1") (pinfunction "P$1_P$1") (pintype "bidirectional"))
      (node (ref "U7") (pin "13") (pinfunction "DTR_13") (pintype "bidirectional"))
      (node (ref "VT5") (pin "2") (pinfunction "E_2") (pintype "passive"))
    )
    (net (code "86") (name "Net-(U7-RTS)") (class "Default")
      (node (ref "R40") (pin "P$1") (pinfunction "P$1_P$1") (pintype "bidirectional"))
      (node (ref "U7") (pin "14") (pinfunction "RTS_14") (pintype "bidirectional"))
      (node (ref "VT6") (pin "2") (pinfunction "E_2") (pintype "passive"))
    )
    (net (code "87") (name "Net-(U7-XI)") (class "Default")
      (node (ref "C26") (pin "P$2") (pinfunction "P$2_P$2") (pintype "bidirectional"))
      (node (ref "U7") (pin "7") (pinfunction "XI_7") (pintype "input"))
      (node (ref "Z1") (pin "1") (pinfunction "1_1") (pintype "passive"))
    )
    (net (code "88") (name "Net-(U7-XO)") (class "Default")
      (node (ref "C27") (pin "P$2") (pinfunction "P$2_P$2") (pintype "bidirectional"))
      (node (ref "U7") (pin "8") (pinfunction "XO_8") (pintype "output"))
      (node (ref "Z1") (pin "3") (pinfunction "2_3") (pintype "passive"))
    )
    (net (code "89") (name "Net-(U8-STBY)") (class "Default")
      (node (ref "C41") (pin "P$2") (pinfunction "P$2_P$2") (pintype "bidirectional"))
      (node (ref "R57") (pin "P$1") (pinfunction "P$1_P$1") (pintype "bidirectional"))
      (node (ref "U8") (pin "19") (pinfunction "STBY_19") (pintype "input"))
      (node (ref "U8") (pin "20") (pinfunction "VCC_20") (pintype "power_in"))
    )
    (net (code "90") (name "Net-(U9-STBY)") (class "Default")
      (node (ref "C16") (pin "P$2") (pinfunction "P$2_P$2") (pintype "bidirectional"))
      (node (ref "R58") (pin "P$1") (pinfunction "P$1_P$1") (pintype "bidirectional"))
      (node (ref "U9") (pin "19") (pinfunction "STBY_19") (pintype "input"))
      (node (ref "U9") (pin "20") (pinfunction "VCC_20") (pintype "power_in"))
    )
    (net (code "91") (name "Net-(U10-AD0{slash}SDO)") (class "Default")
      (node (ref "R21") (pin "P$1") (pinfunction "P$1_P$1") (pintype "bidirectional"))
      (node (ref "U10") (pin "9") (pinfunction "AD0/SDO_9") (pintype "output"))
    )
    (net (code "92") (name "Net-(U10-FSYNC)") (class "Default")
      (node (ref "R14") (pin "P$2") (pinfunction "P$2_P$2") (pintype "bidirectional"))
      (node (ref "R15") (pin "P$1") (pinfunction "P$1_P$1") (pintype "bidirectional"))
      (node (ref "U10") (pin "11") (pinfunction "FSYNC_11") (pintype "input"))
    )
    (net (code "93") (name "Net-(U10-INT)") (class "Default")
      (node (ref "R35") (pin "P$2") (pinfunction "P$2_P$2") (pintype "bidirectional"))
      (node (ref "U10") (pin "12") (pinfunction "INT_12") (pintype "output"))
    )
    (net (code "94") (name "Net-(U10-REGOUT)") (class "Default")
      (node (ref "C12") (pin "P$2") (pinfunction "P$2_P$2") (pintype "bidirectional"))
      (node (ref "U10") (pin "10") (pinfunction "REGOUT_10") (pintype "output"))
    )
    (net (code "95") (name "Net-(U10-RESV_1)") (class "Default")
      (node (ref "R22") (pin "P$1") (pinfunction "P$1_P$1") (pintype "bidirectional"))
      (node (ref "U10") (pin "1") (pinfunction "RESV_1_1") (pintype "passive"))
    )
    (net (code "96") (name "Net-(U10-VDD)") (class "Default")
      (node (ref "C10") (pin "P$2") (pinfunction "P$2_P$2") (pintype "bidirectional"))
      (node (ref "C11") (pin "P$2") (pinfunction "P$2_P$2") (pintype "bidirectional"))
      (node (ref "R12") (pin "P$1") (pinfunction "P$1_P$1") (pintype "bidirectional"))
      (node (ref "R14") (pin "P$1") (pinfunction "P$1_P$1") (pintype "bidirectional"))
      (node (ref "R22") (pin "P$2") (pinfunction "P$2_P$2") (pintype "bidirectional"))
      (node (ref "U10") (pin "13") (pinfunction "VDD_13") (pintype "power_in"))
      (node (ref "U10") (pin "22") (pinfunction "~{CS}_22") (pintype "input"))
      (node (ref "U10") (pin "8") (pinfunction "VDDIO_8") (pintype "power_in"))
    )
    (net (code "97") (name "Net-(USB1-Pad2)") (class "Default")
      (node (ref "USB1") (pin "2") (pinfunction "2_2") (pintype "passive"))
      (node (ref "USB1") (pin "3") (pinfunction "3_3") (pintype "passive"))
    )
    (net (code "98") (name "Net-(USB2-1)") (class "Default")
      (node (ref "R3") (pin "P$2") (pinfunction "P$2_P$2") (pintype "bidirectional"))
      (node (ref "USB2") (pin "P$1.5V") (pinfunction "1_P$1.5V") (pintype "passive"))
    )
    (net (code "99") (name "Net-(VT1-B)") (class "Default")
      (node (ref "R25") (pin "P$1") (pinfunction "P$1_P$1") (pintype "bidirectional"))
      (node (ref "R29") (pin "P$2") (pinfunction "P$2_P$2") (pintype "bidirectional"))
      (node (ref "VT1") (pin "1") (pinfunction "B_1") (pintype "passive"))
    )
    (net (code "100") (name "Net-(VT1-C)") (class "Default")
      (node (ref "VD6") (pin "A") (pinfunction "A_A") (pintype "passive"))
      (node (ref "VT1") (pin "3") (pinfunction "C_3") (pintype "passive"))
      (node (ref "X10") (pin "2") (pinfunction "2_2") (pintype "passive"))
    )
    (net (code "101") (name "Net-(VT2-B)") (class "Default")
      (node (ref "R30") (pin "P$1") (pinfunction "P$1_P$1") (pintype "bidirectional"))
      (node (ref "R31") (pin "P$2") (pinfunction "P$2_P$2") (pintype "bidirectional"))
      (node (ref "VT2") (pin "1") (pinfunction "B_1") (pintype "passive"))
    )
    (net (code "102") (name "Net-(VT2-C)") (class "Default")
      (node (ref "VD7") (pin "A") (pinfunction "A_A") (pintype "passive"))
      (node (ref "VT2") (pin "3") (pinfunction "C_3") (pintype "passive"))
      (node (ref "X11") (pin "2") (pinfunction "2_2") (pintype "passive"))
    )
    (net (code "103") (name "Net-(VT3-B)") (class "Default")
      (node (ref "R32") (pin "P$1") (pinfunction "P$1_P$1") (pintype "bidirectional"))
      (node (ref "R34") (pin "P$2") (pinfunction "P$2_P$2") (pintype "bidirectional"))
      (node (ref "VT3") (pin "1") (pinfunction "B_1") (pintype "passive"))
    )
    (net (code "104") (name "Net-(VT3-C)") (class "Default")
      (node (ref "VD8") (pin "A") (pinfunction "A_A") (pintype "passive"))
      (node (ref "VT3") (pin "3") (pinfunction "C_3") (pintype "passive"))
      (node (ref "X12") (pin "2") (pinfunction "2_2") (pintype "passive"))
    )
    (net (code "105") (name "Net-(VT4-B)") (class "Default")
      (node (ref "R36") (pin "P$1") (pinfunction "P$1_P$1") (pintype "bidirectional"))
      (node (ref "R37") (pin "P$2") (pinfunction "P$2_P$2") (pintype "bidirectional"))
      (node (ref "VT4") (pin "1") (pinfunction "B_1") (pintype "passive"))
    )
    (net (code "106") (name "Net-(VT4-C)") (class "Default")
      (node (ref "VD5") (pin "A") (pinfunction "A_A") (pintype "passive"))
      (node (ref "VT4") (pin "3") (pinfunction "C_3") (pintype "passive"))
      (node (ref "X13") (pin "2") (pinfunction "2_2") (pintype "passive"))
    )
    (net (code "107") (name "Net-(VT5-B)") (class "Default")
      (node (ref "R40") (pin "P$2") (pinfunction "P$2_P$2") (pintype "bidirectional"))
      (node (ref "VT5") (pin "1") (pinfunction "B_1") (pintype "passive"))
    )
    (net (code "108") (name "Net-(VT5-C)") (class "Default")
      (node (ref "R28") (pin "P$1") (pinfunction "P$1_P$1") (pintype "bidirectional"))
      (node (ref "VT5") (pin "3") (pinfunction "C_3") (pintype "passive"))
    )
    (net (code "109") (name "Net-(VT6-B)") (class "Default")
      (node (ref "R41") (pin "P$2") (pinfunction "P$2_P$2") (pintype "bidirectional"))
      (node (ref "VT6") (pin "1") (pinfunction "B_1") (pintype "passive"))
    )
    (net (code "110") (name "Net-(VT6-C)") (class "Default")
      (node (ref "R45") (pin "P$2") (pinfunction "P$2_P$2") (pintype "bidirectional"))
      (node (ref "VT6") (pin "3") (pinfunction "C_3") (pintype "passive"))
    )
    (net (code "111") (name "Net-(VT7-B)") (class "Default")
      (node (ref "R43") (pin "P$1") (pinfunction "P$1_P$1") (pintype "bidirectional"))
      (node (ref "R46") (pin "P$2") (pinfunction "P$2_P$2") (pintype "bidirectional"))
      (node (ref "VT7") (pin "1") (pinfunction "B_1") (pintype "passive"))
    )
    (net (code "112") (name "Net-(VT7-C)") (class "Default")
      (node (ref "VD4") (pin "A") (pinfunction "A_A") (pintype "passive"))
      (node (ref "VT7") (pin "3") (pinfunction "C_3") (pintype "passive"))
      (node (ref "X14") (pin "2") (pinfunction "2_2") (pintype "passive"))
    )
    (net (code "113") (name "PWM_D_OUT_1") (class "Default")
      (node (ref "U2") (pin "12") (pinfunction "PA2_12") (pintype "bidirectional"))
      (node (ref "U8") (pin "23") (pinfunction "PWMA_23") (pintype "input"))
    )
    (net (code "114") (name "PWM_D_OUT_2") (class "Default")
      (node (ref "U2") (pin "13") (pinfunction "PA3_13") (pintype "bidirectional"))
      (node (ref "U8") (pin "15") (pinfunction "PWMB_15") (pintype "input"))
    )
    (net (code "115") (name "PWM_D_OUT_3") (class "Default")
      (node (ref "U2") (pin "18") (pinfunction "PB0_18") (pintype "bidirectional"))
      (node (ref "U9") (pin "23") (pinfunction "PWMA_23") (pintype "input"))
    )
    (net (code "116") (name "PWM_D_OUT_4") (class "Default")
      (node (ref "U2") (pin "19") (pinfunction "PB1_19") (pintype "bidirectional"))
      (node (ref "U9") (pin "15") (pinfunction "PWMB_15") (pintype "input"))
    )
    (net (code "117") (name "RESET_ESP") (class "Default")
      (node (ref "C17") (pin "P$2") (pinfunction "P$2_P$2") (pintype "bidirectional"))
      (node (ref "R17") (pin "P$2") (pinfunction "P$2_P$2") (pintype "bidirectional"))
      (node (ref "R24") (pin "P$2") (pinfunction "P$2_P$2") (pintype "bidirectional"))
      (node (ref "R45") (pin "P$1") (pinfunction "P$1_P$1") (pintype "bidirectional"))
      (node (ref "U1") (pin "3") (pinfunction "EN_3") (pintype "bidirectional"))
    )
    (net (code "118") (name "RXD") (class "Default")
      (node (ref "R38") (pin "P$1") (pinfunction "P$1_P$1") (pintype "bidirectional"))
      (node (ref "U1") (pin "35") (pinfunction "TXD0_35") (pintype "bidirectional"))
      (node (ref "U7") (pin "3") (pinfunction "RX_3") (pintype "input"))
    )
    (net (code "119") (name "SCL") (class "Default")
      (node (ref "R16") (pin "P$1") (pinfunction "P$1_P$1") (pintype "bidirectional"))
      (node (ref "U1") (pin "33") (pinfunction "IO21_33") (pintype "bidirectional"))
      (node (ref "U10") (pin "23") (pinfunction "SCL/SCLK_23") (pintype "input"))
    )
    (net (code "120") (name "SDA") (class "Default")
      (node (ref "R13") (pin "P$1") (pinfunction "P$1_P$1") (pintype "bidirectional"))
      (node (ref "U1") (pin "36") (pinfunction "IO22_36") (pintype "bidirectional"))
      (node (ref "U10") (pin "24") (pinfunction "SDA/SDI_24") (pintype "bidirectional"))
    )
    (net (code "121") (name "SERV_1") (class "Default")
      (node (ref "R47") (pin "P$2") (pinfunction "P$2_P$2") (pintype "bidirectional"))
      (node (ref "U1") (pin "10") (pinfunction "IO25_10") (pintype "bidirectional"))
      (node (ref "VD9") (pin "3") (pinfunction "I/O_3") (pintype "bidirectional"))
      (node (ref "ZD5") (pin "C") (pinfunction "C_C") (pintype "passive"))
    )
    (net (code "122") (name "SERV_2") (class "Default")
      (node (ref "R48") (pin "P$2") (pinfunction "P$2_P$2") (pintype "bidirectional"))
      (node (ref "U1") (pin "9") (pinfunction "IO33_9") (pintype "bidirectional"))
      (node (ref "VD10") (pin "3") (pinfunction "I/O_3") (pintype "bidirectional"))
      (node (ref "ZD6") (pin "C") (pinfunction "C_C") (pintype "passive"))
    )
    (net (code "123") (name "TXD") (class "Default")
      (node (ref "R39") (pin "P$1") (pinfunction "P$1_P$1") (pintype "bidirectional"))
      (node (ref "U1") (pin "34") (pinfunction "RXD0_34") (pintype "bidirectional"))
      (node (ref "U7") (pin "2") (pinfunction "TX_2") (pintype "output"))
    )
    (net (code "124") (name "UART_RX") (class "Default")
      (node (ref "U1") (pin "30") (pinfunction "IO18_30") (pintype "bidirectional"))
      (node (ref "U2") (pin "22") (pinfunction "PB11_22") (pintype "bidirectional"))
    )
    (net (code "125") (name "UART_TX") (class "Default")
      (node (ref "U1") (pin "28") (pinfunction "IO17_28") (pintype "bidirectional"))
      (node (ref "U2") (pin "21") (pinfunction "PB10_21") (pintype "bidirectional"))
    )
    (net (code "126") (name "U_ACUM") (class "Default")
      (node (ref "R5") (pin "P$1") (pinfunction "P$1_P$1") (pintype "bidirectional"))
      (node (ref "R6") (pin "P$2") (pinfunction "P$2_P$2") (pintype "bidirectional"))
      (node (ref "U1") (pin "4") (pinfunction "SENSOR_VP_4") (pintype "input"))
      (node (ref "ZD3") (pin "C") (pinfunction "C_C") (pintype "passive"))
    )
    (net (code "127") (name "VIN+") (class "Default")
      (node (ref "C20") (pin "P$2") (pinfunction "P$2_P$2") (pintype "bidirectional"))
      (node (ref "C21") (pin "P$2") (pinfunction "P$2_P$2") (pintype "bidirectional"))
      (node (ref "C22") (pin "P$2") (pinfunction "P$2_P$2") (pintype "bidirectional"))
      (node (ref "C28") (pin "P$2") (pinfunction "P$2_P$2") (pintype "bidirectional"))
      (node (ref "C29") (pin "P$2") (pinfunction "P$2_P$2") (pintype "bidirectional"))
      (node (ref "C3") (pin "P$2") (pinfunction "P$2_P$2") (pintype "bidirectional"))
      (node (ref "C4") (pin "P$2") (pinfunction "P$2_P$2") (pintype "bidirectional"))
      (node (ref "R4") (pin "2") (pinfunction "P$2_2") (pintype "bidirectional"))
      (node (ref "R5") (pin "P$2") (pinfunction "P$2_P$2") (pintype "bidirectional"))
      (node (ref "U4") (pin "+I") (pinfunction "+VIN_+I") (pintype "bidirectional"))
      (node (ref "U8") (pin "13") (pinfunction "VM2_13") (pintype "power_in"))
      (node (ref "U8") (pin "14") (pinfunction "VM3_14") (pintype "power_in"))
      (node (ref "U8") (pin "24") (pinfunction "VM1_24") (pintype "power_in"))
      (node (ref "U9") (pin "13") (pinfunction "VM2_13") (pintype "power_in"))
      (node (ref "U9") (pin "14") (pinfunction "VM3_14") (pintype "power_in"))
      (node (ref "U9") (pin "24") (pinfunction "VM1_24") (pintype "power_in"))
      (node (ref "VD6") (pin "C") (pinfunction "C_C") (pintype "passive"))
      (node (ref "VD7") (pin "C") (pinfunction "C_C") (pintype "passive"))
      (node (ref "VD8") (pin "C") (pinfunction "C_C") (pintype "passive"))
      (node (ref "X10") (pin "1") (pinfunction "1_1") (pintype "passive"))
      (node (ref "X11") (pin "1") (pinfunction "1_1") (pintype "passive"))
      (node (ref "X12") (pin "1") (pinfunction "1_1") (pintype "passive"))
      (node (ref "ZD1") (pin "C") (pinfunction "C_C") (pintype "passive"))
    )
    (net (code "128") (name "unconnected-(S1-Pad2)") (class "Default")
      (node (ref "S1") (pin "2") (pinfunction "2_2") (pintype "passive"))
    )
    (net (code "129") (name "unconnected-(S2-Pad2)") (class "Default")
      (node (ref "S2") (pin "2") (pinfunction "2_2") (pintype "passive"))
    )
    (net (code "130") (name "unconnected-(S3-Pad2)") (class "Default")
      (node (ref "S3") (pin "2") (pinfunction "2_2") (pintype "passive"))
    )
    (net (code "131") (name "unconnected-(S3-Pad4)") (class "Default")
      (node (ref "S3") (pin "4") (pinfunction "4_4") (pintype "passive"))
    )
    (net (code "132") (name "unconnected-(U1-CLK-Pad20)") (class "Default")
      (node (ref "U1") (pin "20") (pinfunction "CLK_20") (pintype "bidirectional"))
    )
    (net (code "133") (name "unconnected-(U1-CMD-Pad19)") (class "Default")
      (node (ref "U1") (pin "19") (pinfunction "CMD_19") (pintype "bidirectional"))
    )
    (net (code "134") (name "unconnected-(U1-IO2-Pad24)") (class "Default")
      (node (ref "U1") (pin "24") (pinfunction "IO2_24") (pintype "bidirectional"))
    )
    (net (code "135") (name "unconnected-(U1-IO4-Pad26)") (class "Default")
      (node (ref "U1") (pin "26") (pinfunction "IO4_26") (pintype "bidirectional"))
    )
    (net (code "136") (name "unconnected-(U1-IO5-Pad29)") (class "Default")
      (node (ref "U1") (pin "29") (pinfunction "IO5_29") (pintype "bidirectional"))
    )
    (net (code "137") (name "unconnected-(U1-IO12-Pad14)") (class "Default")
      (node (ref "U1") (pin "14") (pinfunction "IO12_14") (pintype "bidirectional"))
    )
    (net (code "138") (name "unconnected-(U1-IO13-Pad16)") (class "Default")
      (node (ref "U1") (pin "16") (pinfunction "IO13_16") (pintype "bidirectional"))
    )
    (net (code "139") (name "unconnected-(U1-IO14-Pad13)") (class "Default")
      (node (ref "U1") (pin "13") (pinfunction "IO14_13") (pintype "bidirectional"))
    )
    (net (code "140") (name "unconnected-(U1-IO15-Pad23)") (class "Default")
      (node (ref "U1") (pin "23") (pinfunction "IO15_23") (pintype "bidirectional"))
    )
    (net (code "141") (name "unconnected-(U1-IO32-Pad8)") (class "Default")
      (node (ref "U1") (pin "8") (pinfunction "IO32_8") (pintype "bidirectional"))
    )
    (net (code "142") (name "unconnected-(U1-IO34-Pad6)") (class "Default")
      (node (ref "U1") (pin "6") (pinfunction "IO34_6") (pintype "input"))
    )
    (net (code "143") (name "unconnected-(U1-IO35-Pad7)") (class "Default")
      (node (ref "U1") (pin "7") (pinfunction "IO35_7") (pintype "input"))
    )
    (net (code "144") (name "unconnected-(U1-NC-Pad32)") (class "Default")
      (node (ref "U1") (pin "32") (pinfunction "NC_32") (pintype "bidirectional"))
    )
    (net (code "145") (name "unconnected-(U1-SD1-Pad22)") (class "Default")
      (node (ref "U1") (pin "22") (pinfunction "SD1_22") (pintype "bidirectional"))
    )
    (net (code "146") (name "unconnected-(U1-SD2-Pad17)") (class "Default")
      (node (ref "U1") (pin "17") (pinfunction "SD2_17") (pintype "bidirectional"))
    )
    (net (code "147") (name "unconnected-(U1-SD3-Pad18)") (class "Default")
      (node (ref "U1") (pin "18") (pinfunction "SD3_18") (pintype "bidirectional"))
    )
    (net (code "148") (name "unconnected-(U1-SDO-Pad21)") (class "Default")
      (node (ref "U1") (pin "21") (pinfunction "SDO_21") (pintype "bidirectional"))
    )
    (net (code "149") (name "unconnected-(U2-PB2-Pad20)") (class "Default")
      (node (ref "U2") (pin "20") (pinfunction "PB2_20") (pintype "bidirectional"))
    )
    (net (code "150") (name "unconnected-(U2-PB8-Pad45)") (class "Default")
      (node (ref "U2") (pin "45") (pinfunction "PB8_45") (pintype "bidirectional"))
    )
    (net (code "151") (name "unconnected-(U2-PB9-Pad46)") (class "Default")
      (node (ref "U2") (pin "46") (pinfunction "PB9_46") (pintype "bidirectional"))
    )
    (net (code "152") (name "unconnected-(U2-PC15-OSC32_OUT-Pad4)") (class "Default")
      (node (ref "U2") (pin "4") (pinfunction "PC15-OSC32_OUT_4") (pintype "bidirectional"))
    )
    (net (code "153") (name "unconnected-(U3-LBK-Pad5)") (class "Default")
      (node (ref "U3") (pin "5") (pinfunction "LBK_5") (pintype "bidirectional"))
    )
    (net (code "154") (name "unconnected-(U6B-OUT2-Pad7)") (class "Default")
      (node (ref "U6") (pin "7") (pinfunction "OUT2_7") (pintype "output"))
    )
    (net (code "155") (name "unconnected-(U7-CTS-Pad9)") (class "Default")
      (node (ref "U7") (pin "9") (pinfunction "CTS_9") (pintype "bidirectional"))
    )
    (net (code "156") (name "unconnected-(U7-DCD-Pad12)") (class "Default")
      (node (ref "U7") (pin "12") (pinfunction "DCD_12") (pintype "bidirectional"))
    )
    (net (code "157") (name "unconnected-(U7-DSR-Pad10)") (class "Default")
      (node (ref "U7") (pin "10") (pinfunction "DSR_10") (pintype "bidirectional"))
    )
    (net (code "158") (name "unconnected-(U7-R232-Pad15)") (class "Default")
      (node (ref "U7") (pin "15") (pinfunction "R232_15") (pintype "bidirectional"))
    )
    (net (code "159") (name "unconnected-(U7-RI-Pad11)") (class "Default")
      (node (ref "U7") (pin "11") (pinfunction "RI_11") (pintype "bidirectional"))
    )
    (net (code "160") (name "unconnected-(U10-AUX_CL-Pad7)") (class "Default")
      (node (ref "U10") (pin "7") (pinfunction "AUX_CL_7") (pintype "input"))
    )
    (net (code "161") (name "unconnected-(U10-AUX_DA-Pad21)") (class "Default")
      (node (ref "U10") (pin "21") (pinfunction "AUX_DA_21") (pintype "input"))
    )
    (net (code "162") (name "unconnected-(U10-RESV_19-Pad19)") (class "Default")
      (node (ref "U10") (pin "19") (pinfunction "RESV_19_19") (pintype "passive"))
    )
  )
)
